# stm32.net
KiCad netlist of a schematic drawn in EasyEDA Pro
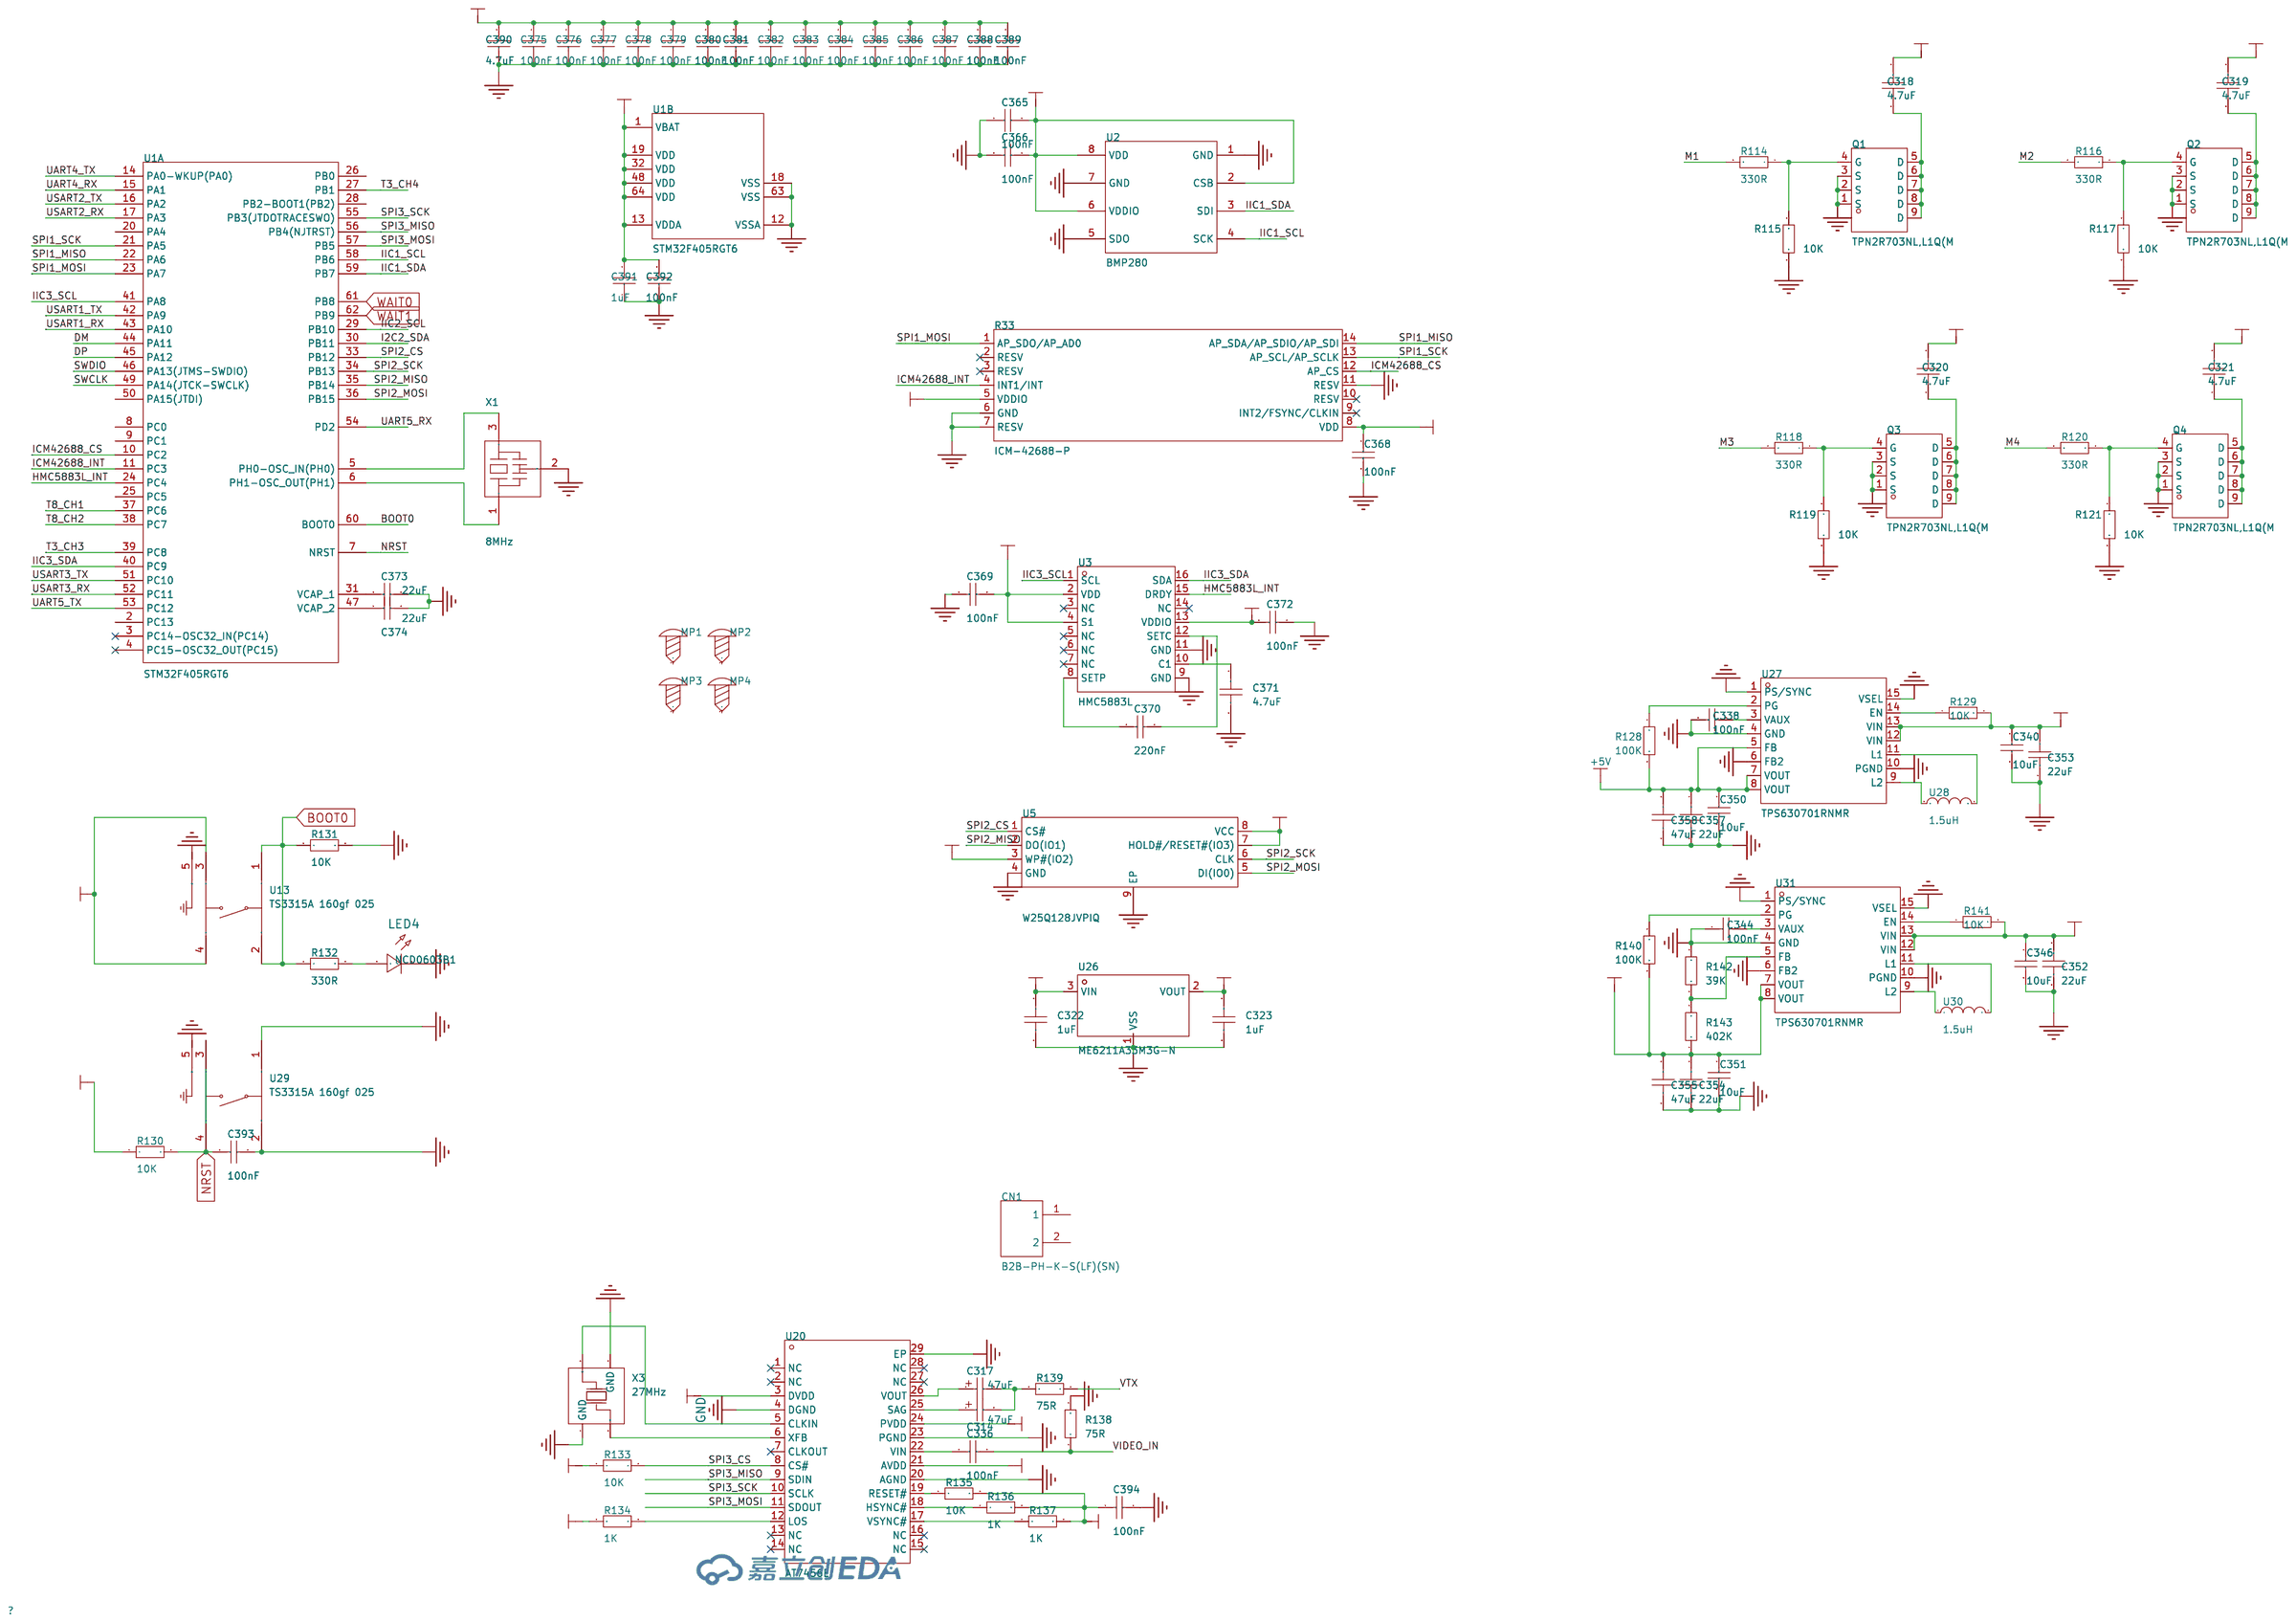
[diagram p0: P1]
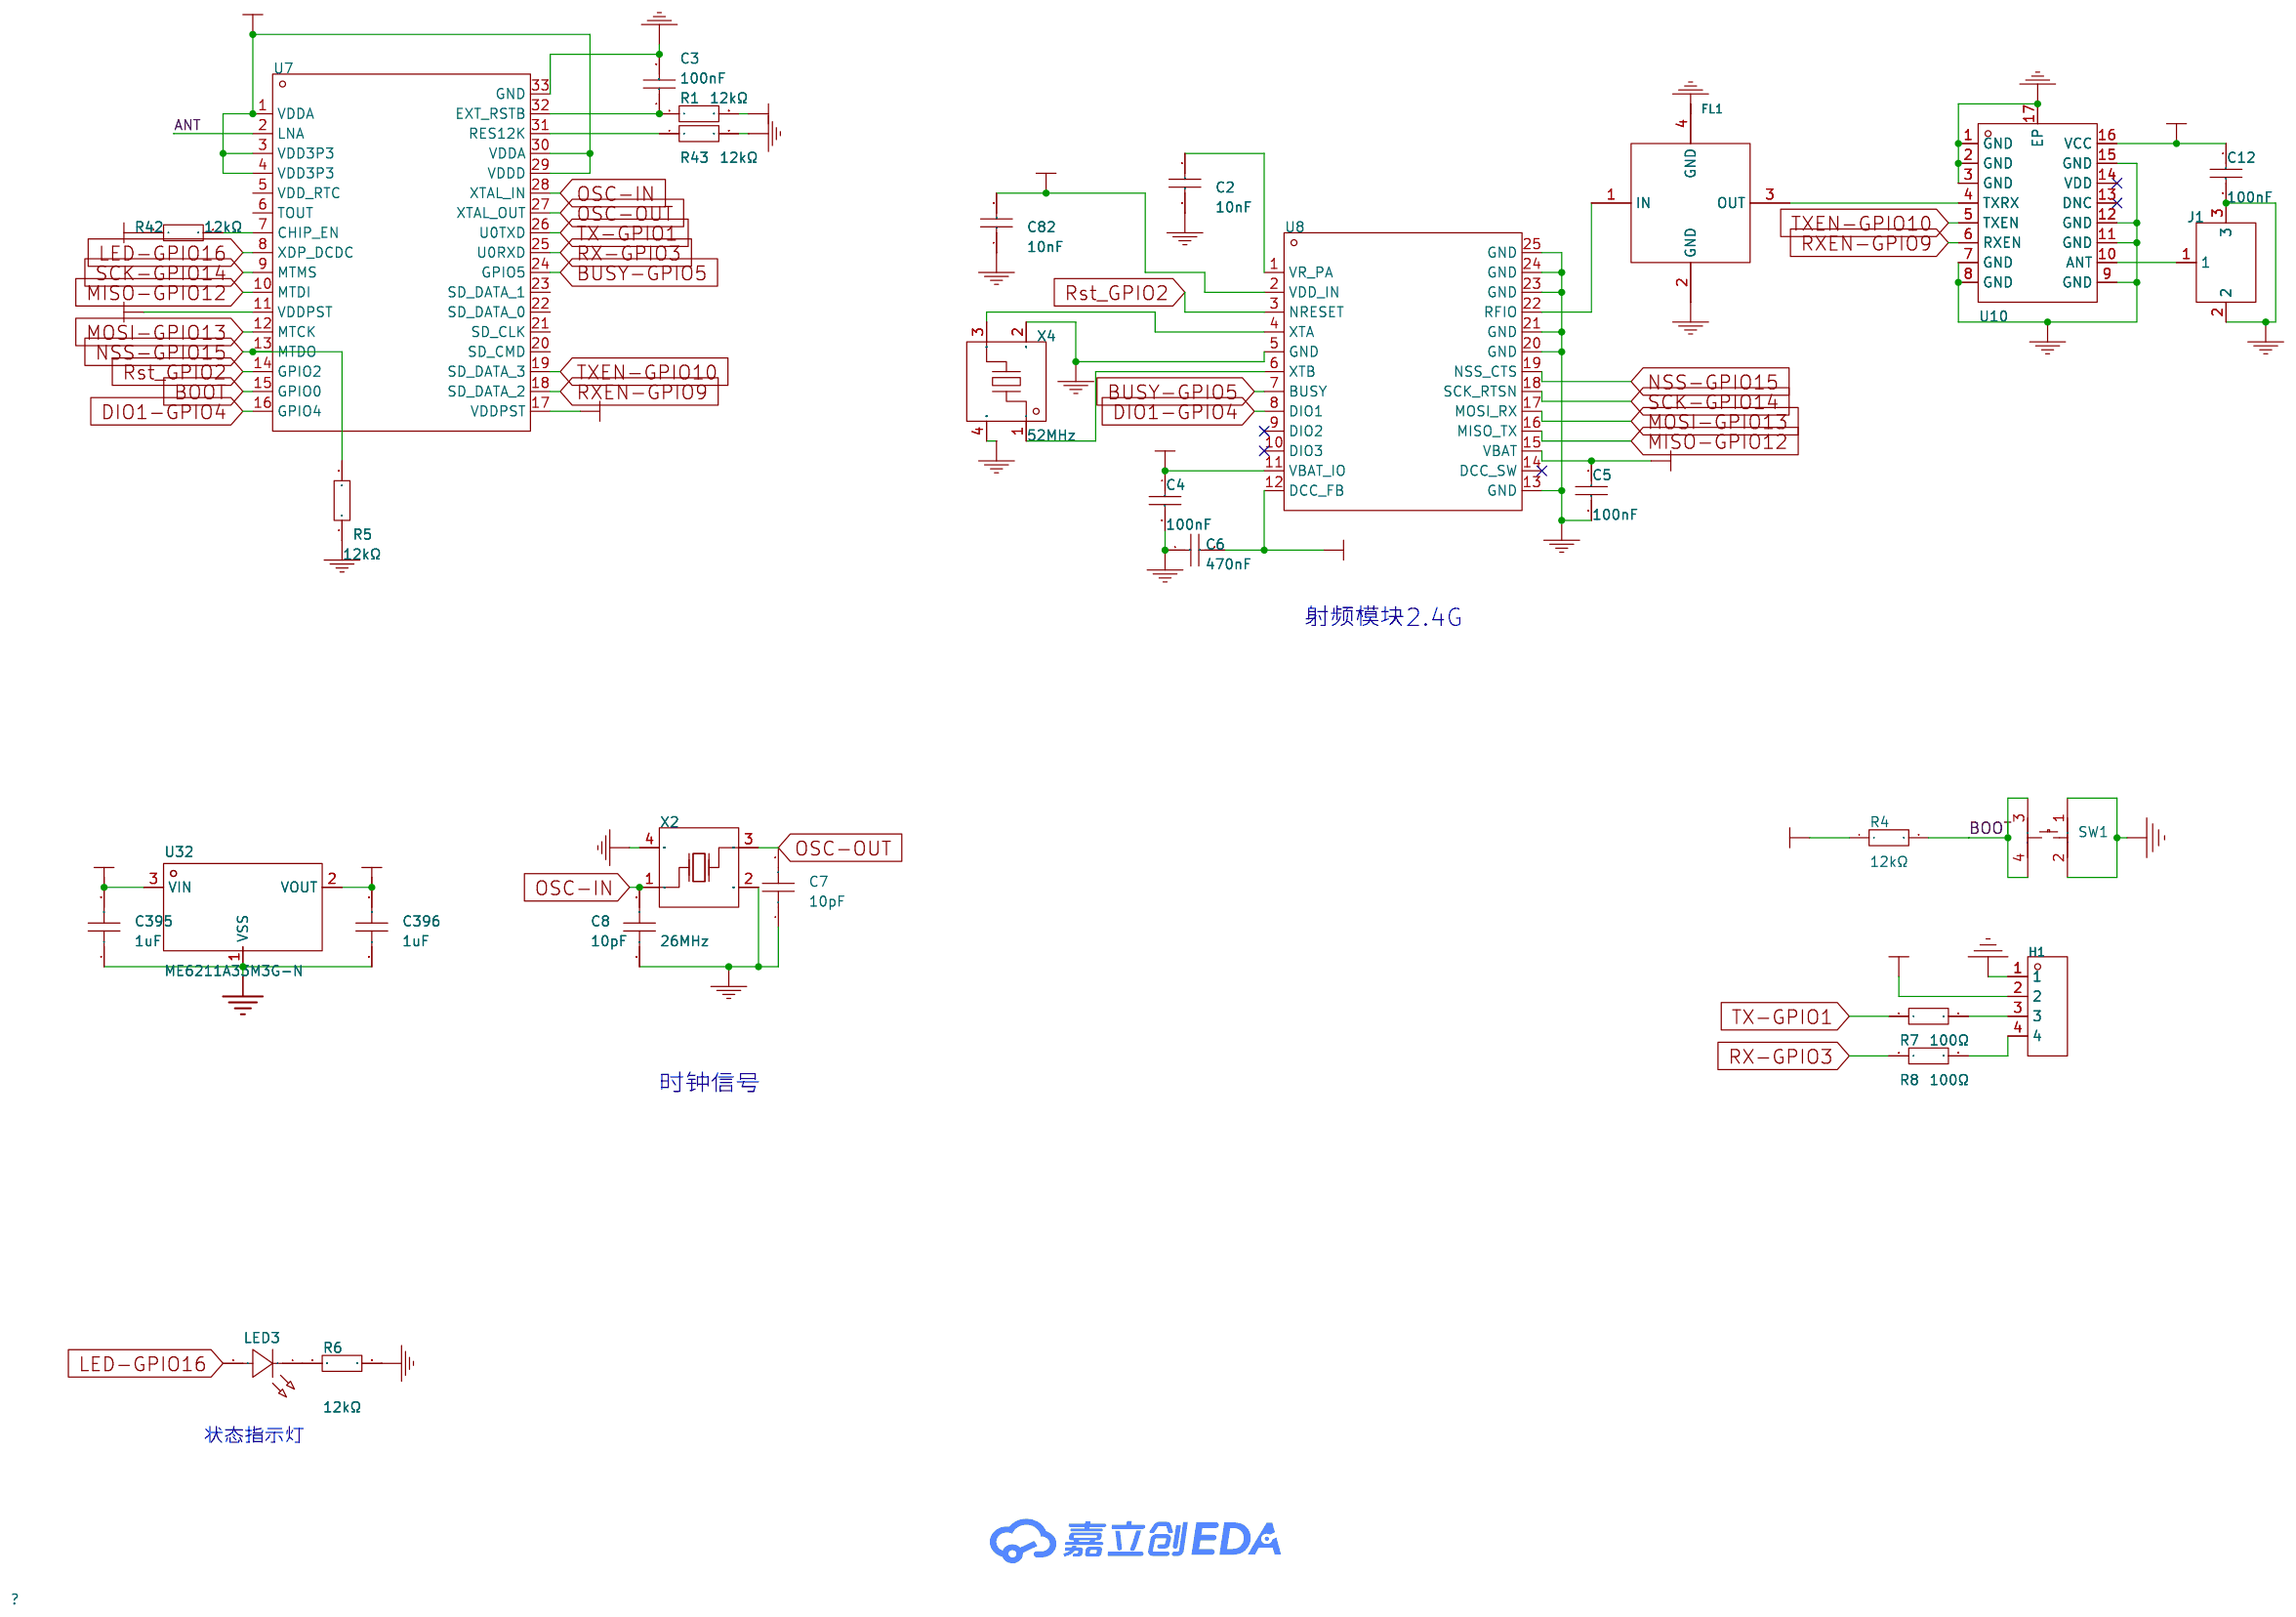
[diagram p1: P2]

(export (version "E")
  (design (tool "Eeschema 10.0.6"))
  (components
    (comp (ref "C314")
      (value "47uF")
      (footprint "easyedapro:CAP-SMD_L3.2-W1.6-RD")
      (description "容值:47uF;精度:±10%;额定电压:6.3V;等效串联电阻:2.5Ω@100kHz;")
      (fields (field (name "Manufacturer Part") "TC212A476K006Y") (field (name "Manufacturer") "Sunlord(顺络)"))
      (libsource (lib "easyedapro") (part "TC212A476K006Y"))
    )
    (comp (ref "C317")
      (value "47uF")
      (footprint "easyedapro:CAP-SMD_L3.2-W1.6-RD")
      (description "容值:47uF;精度:±10%;额定电压:6.3V;等效串联电阻:2.5Ω@100kHz;")
      (fields (field (name "Manufacturer Part") "TC212A476K006Y") (field (name "Manufacturer") "Sunlord(顺络)"))
      (libsource (lib "easyedapro") (part "TC212A476K006Y"))
    )
    (comp (ref "C318")
      (value "4.7uF")
      (footprint "easyedapro:C0805")
      (libsource (lib "easyedapro") (part "Capacitance"))
    )
    (comp (ref "C319")
      (value "4.7uF")
      (footprint "easyedapro:C0805")
      (libsource (lib "easyedapro") (part "Capacitance"))
    )
    (comp (ref "C320")
      (value "4.7uF")
      (footprint "easyedapro:C0805")
      (libsource (lib "easyedapro") (part "Capacitance"))
    )
    (comp (ref "C321")
      (value "4.7uF")
      (footprint "easyedapro:C0805")
      (libsource (lib "easyedapro") (part "Capacitance"))
    )
    (comp (ref "C322")
      (value "1uF")
      (footprint "easyedapro:C0402")
      (description "容值:10pF;精度:±5%;额定电压:50V;材质(温度系数):C0G;")
      (fields
        (field (name "Manufacturer Part") "CL05C100JB5NNNC")
        (field (name "Manufacturer") "SAMSUNG(三星)")
      )
      (libsource (lib "easyedapro") (part "CL05C100JB5NNNC"))
    )
    (comp (ref "C323")
      (value "1uF")
      (footprint "easyedapro:C0402")
      (description "容值:10pF;精度:±5%;额定电压:50V;材质(温度系数):C0G;")
      (fields
        (field (name "Manufacturer Part") "CL05C100JB5NNNC")
        (field (name "Manufacturer") "SAMSUNG(三星)")
      )
      (libsource (lib "easyedapro") (part "CL05C100JB5NNNC"))
    )
    (comp (ref "C336")
      (value "100nF")
      (footprint "easyedapro:C0402")
      (description "容值:100nF;精度:±10%;额定电压:16V;材质(温度系数):X7R;")
      (fields
        (field (name "Manufacturer Part") "CL05B104KO5NNNC")
        (field (name "Manufacturer") "SAMSUNG(三星)")
      )
      (libsource (lib "easyedapro") (part "CL05B104KO5NNNC"))
    )
    (comp (ref "C338")
      (value "100nF")
      (footprint "easyedapro:C0402")
      (description "容值:100nF;精度:±10%;额定电压:16V;材质(温度系数):X7R;")
      (fields
        (field (name "Manufacturer Part") "CL05B104KO5NNNC")
        (field (name "Manufacturer") "SAMSUNG(三星)")
      )
      (libsource (lib "easyedapro") (part "CL05B104KO5NNNC"))
    )
    (comp (ref "C340")
      (value "10uF")
      (footprint "easyedapro:C0402")
      (description "容值:100nF;精度:±10%;额定电压:16V;材质(温度系数):X7R;")
      (fields
        (field (name "Manufacturer Part") "CL05B104KO5NNNC")
        (field (name "Manufacturer") "SAMSUNG(三星)")
      )
      (libsource (lib "easyedapro") (part "CL05B104KO5NNNC"))
    )
    (comp (ref "C344")
      (value "100nF")
      (footprint "easyedapro:C0402")
      (description "容值:100nF;精度:±10%;额定电压:16V;材质(温度系数):X7R;")
      (fields
        (field (name "Manufacturer Part") "CL05B104KO5NNNC")
        (field (name "Manufacturer") "SAMSUNG(三星)")
      )
      (libsource (lib "easyedapro") (part "CL05B104KO5NNNC"))
    )
    (comp (ref "C346")
      (value "10uF")
      (footprint "easyedapro:C0402")
      (description "容值:100nF;精度:±10%;额定电压:16V;材质(温度系数):X7R;")
      (fields
        (field (name "Manufacturer Part") "CL05B104KO5NNNC")
        (field (name "Manufacturer") "SAMSUNG(三星)")
      )
      (libsource (lib "easyedapro") (part "CL05B104KO5NNNC"))
    )
    (comp (ref "C350")
      (value "10uF")
      (footprint "easyedapro:C0402")
      (description "容值:100nF;精度:±10%;额定电压:16V;材质(温度系数):X7R;")
      (fields
        (field (name "Manufacturer Part") "CL05B104KO5NNNC")
        (field (name "Manufacturer") "SAMSUNG(三星)")
      )
      (libsource (lib "easyedapro") (part "CL05B104KO5NNNC"))
    )
    (comp (ref "C351")
      (value "10uF")
      (footprint "easyedapro:C0402")
      (description "容值:100nF;精度:±10%;额定电压:16V;材质(温度系数):X7R;")
      (fields
        (field (name "Manufacturer Part") "CL05B104KO5NNNC")
        (field (name "Manufacturer") "SAMSUNG(三星)")
      )
      (libsource (lib "easyedapro") (part "CL05B104KO5NNNC"))
    )
    (comp (ref "C352")
      (value "22uF")
      (footprint "easyedapro:C0805")
      (libsource (lib "easyedapro") (part "Capacitance"))
    )
    (comp (ref "C353")
      (value "22uF")
      (footprint "easyedapro:C0805")
      (libsource (lib "easyedapro") (part "Capacitance"))
    )
    (comp (ref "C354")
      (value "22uF")
      (footprint "easyedapro:C0805")
      (libsource (lib "easyedapro") (part "Capacitance"))
    )
    (comp (ref "C355")
      (value "47uF")
      (footprint "easyedapro:C0805")
      (libsource (lib "easyedapro") (part "Capacitance"))
    )
    (comp (ref "C357")
      (value "22uF")
      (footprint "easyedapro:C0805")
      (libsource (lib "easyedapro") (part "Capacitance"))
    )
    (comp (ref "C358")
      (value "47uF")
      (footprint "easyedapro:C0805")
      (libsource (lib "easyedapro") (part "Capacitance"))
    )
    (comp (ref "C365")
      (value "100nF")
      (footprint "easyedapro:C0402")
      (description "容值:100nF;精度:±10%;额定电压:16V;材质(温度系数):X7R;")
      (fields
        (field (name "Manufacturer Part") "CL05B104KO5NNNC")
        (field (name "Manufacturer") "SAMSUNG(三星)")
      )
      (libsource (lib "easyedapro") (part "CL05B104KO5NNNC"))
    )
    (comp (ref "C366")
      (value "100nF")
      (footprint "easyedapro:C0402")
      (description "容值:100nF;精度:±10%;额定电压:16V;材质(温度系数):X7R;")
      (fields
        (field (name "Manufacturer Part") "CL05B104KO5NNNC")
        (field (name "Manufacturer") "SAMSUNG(三星)")
      )
      (libsource (lib "easyedapro") (part "CL05B104KO5NNNC"))
    )
    (comp (ref "C368")
      (value "100nF")
      (footprint "easyedapro:C0402")
      (description "容值:100nF;精度:±10%;额定电压:16V;材质(温度系数):X7R;")
      (fields
        (field (name "Manufacturer Part") "CL05B104KO5NNNC")
        (field (name "Manufacturer") "SAMSUNG(三星)")
      )
      (libsource (lib "easyedapro") (part "CL05B104KO5NNNC"))
    )
    (comp (ref "C369")
      (value "100nF")
      (footprint "easyedapro:C0402")
      (description "容值:100nF;精度:±10%;额定电压:16V;材质(温度系数):X7R;")
      (fields
        (field (name "Manufacturer Part") "CL05B104KO5NNNC")
        (field (name "Manufacturer") "SAMSUNG(三星)")
      )
      (libsource (lib "easyedapro") (part "CL05B104KO5NNNC"))
    )
    (comp (ref "C370")
      (value "220nF")
      (footprint "easyedapro:C0402")
      (description "容值:100nF;精度:±10%;额定电压:16V;材质(温度系数):X7R;")
      (fields
        (field (name "Manufacturer Part") "CL05B104KO5NNNC")
        (field (name "Manufacturer") "SAMSUNG(三星)")
      )
      (libsource (lib "easyedapro") (part "CL05B104KO5NNNC"))
    )
    (comp (ref "C371")
      (value "4.7uF")
      (footprint "easyedapro:C0805")
      (libsource (lib "easyedapro") (part "Capacitance"))
    )
    (comp (ref "C372")
      (value "100nF")
      (footprint "easyedapro:C0402")
      (description "容值:100nF;精度:±10%;额定电压:16V;材质(温度系数):X7R;")
      (fields
        (field (name "Manufacturer Part") "CL05B104KO5NNNC")
        (field (name "Manufacturer") "SAMSUNG(三星)")
      )
      (libsource (lib "easyedapro") (part "CL05B104KO5NNNC"))
    )
    (comp (ref "C373")
      (value "22uF")
      (footprint "easyedapro:C0402")
      (description "容值:100nF;精度:±10%;额定电压:16V;材质(温度系数):X7R;")
      (fields
        (field (name "Manufacturer Part") "CL05B104KO5NNNC")
        (field (name "Manufacturer") "SAMSUNG(三星)")
      )
      (libsource (lib "easyedapro") (part "CL05B104KO5NNNC"))
    )
    (comp (ref "C374")
      (value "22uF")
      (footprint "easyedapro:C0402")
      (description "容值:100nF;精度:±10%;额定电压:16V;材质(温度系数):X7R;")
      (fields
        (field (name "Manufacturer Part") "CL05B104KO5NNNC")
        (field (name "Manufacturer") "SAMSUNG(三星)")
      )
      (libsource (lib "easyedapro") (part "CL05B104KO5NNNC"))
    )
    (comp (ref "C375")
      (value "100nF")
      (footprint "easyedapro:C0402")
      (description "容值:100nF;精度:±10%;额定电压:16V;材质(温度系数):X7R;")
      (fields
        (field (name "Manufacturer Part") "CL05B104KO5NNNC")
        (field (name "Manufacturer") "SAMSUNG(三星)")
      )
      (libsource (lib "easyedapro") (part "CL05B104KO5NNNC"))
    )
    (comp (ref "C376")
      (value "100nF")
      (footprint "easyedapro:C0402")
      (description "容值:100nF;精度:±10%;额定电压:16V;材质(温度系数):X7R;")
      (fields
        (field (name "Manufacturer Part") "CL05B104KO5NNNC")
        (field (name "Manufacturer") "SAMSUNG(三星)")
      )
      (libsource (lib "easyedapro") (part "CL05B104KO5NNNC"))
    )
    (comp (ref "C377")
      (value "100nF")
      (footprint "easyedapro:C0402")
      (description "容值:100nF;精度:±10%;额定电压:16V;材质(温度系数):X7R;")
      (fields
        (field (name "Manufacturer Part") "CL05B104KO5NNNC")
        (field (name "Manufacturer") "SAMSUNG(三星)")
      )
      (libsource (lib "easyedapro") (part "CL05B104KO5NNNC"))
    )
    (comp (ref "C378")
      (value "100nF")
      (footprint "easyedapro:C0402")
      (description "容值:100nF;精度:±10%;额定电压:16V;材质(温度系数):X7R;")
      (fields
        (field (name "Manufacturer Part") "CL05B104KO5NNNC")
        (field (name "Manufacturer") "SAMSUNG(三星)")
      )
      (libsource (lib "easyedapro") (part "CL05B104KO5NNNC"))
    )
    (comp (ref "C379")
      (value "100nF")
      (footprint "easyedapro:C0402")
      (description "容值:100nF;精度:±10%;额定电压:16V;材质(温度系数):X7R;")
      (fields
        (field (name "Manufacturer Part") "CL05B104KO5NNNC")
        (field (name "Manufacturer") "SAMSUNG(三星)")
      )
      (libsource (lib "easyedapro") (part "CL05B104KO5NNNC"))
    )
    (comp (ref "C380")
      (value "100nF")
      (footprint "easyedapro:C0402")
      (description "容值:100nF;精度:±10%;额定电压:16V;材质(温度系数):X7R;")
      (fields
        (field (name "Manufacturer Part") "CL05B104KO5NNNC")
        (field (name "Manufacturer") "SAMSUNG(三星)")
      )
      (libsource (lib "easyedapro") (part "CL05B104KO5NNNC"))
    )
    (comp (ref "C381")
      (value "100nF")
      (footprint "easyedapro:C0402")
      (description "容值:100nF;精度:±10%;额定电压:16V;材质(温度系数):X7R;")
      (fields
        (field (name "Manufacturer Part") "CL05B104KO5NNNC")
        (field (name "Manufacturer") "SAMSUNG(三星)")
      )
      (libsource (lib "easyedapro") (part "CL05B104KO5NNNC"))
    )
    (comp (ref "C382")
      (value "100nF")
      (footprint "easyedapro:C0402")
      (description "容值:100nF;精度:±10%;额定电压:16V;材质(温度系数):X7R;")
      (fields
        (field (name "Manufacturer Part") "CL05B104KO5NNNC")
        (field (name "Manufacturer") "SAMSUNG(三星)")
      )
      (libsource (lib "easyedapro") (part "CL05B104KO5NNNC"))
    )
    (comp (ref "C383")
      (value "100nF")
      (footprint "easyedapro:C0402")
      (description "容值:100nF;精度:±10%;额定电压:16V;材质(温度系数):X7R;")
      (fields
        (field (name "Manufacturer Part") "CL05B104KO5NNNC")
        (field (name "Manufacturer") "SAMSUNG(三星)")
      )
      (libsource (lib "easyedapro") (part "CL05B104KO5NNNC"))
    )
    (comp (ref "C384")
      (value "100nF")
      (footprint "easyedapro:C0402")
      (description "容值:100nF;精度:±10%;额定电压:16V;材质(温度系数):X7R;")
      (fields
        (field (name "Manufacturer Part") "CL05B104KO5NNNC")
        (field (name "Manufacturer") "SAMSUNG(三星)")
      )
      (libsource (lib "easyedapro") (part "CL05B104KO5NNNC"))
    )
    (comp (ref "C385")
      (value "100nF")
      (footprint "easyedapro:C0402")
      (description "容值:100nF;精度:±10%;额定电压:16V;材质(温度系数):X7R;")
      (fields
        (field (name "Manufacturer Part") "CL05B104KO5NNNC")
        (field (name "Manufacturer") "SAMSUNG(三星)")
      )
      (libsource (lib "easyedapro") (part "CL05B104KO5NNNC"))
    )
    (comp (ref "C386")
      (value "100nF")
      (footprint "easyedapro:C0402")
      (description "容值:100nF;精度:±10%;额定电压:16V;材质(温度系数):X7R;")
      (fields
        (field (name "Manufacturer Part") "CL05B104KO5NNNC")
        (field (name "Manufacturer") "SAMSUNG(三星)")
      )
      (libsource (lib "easyedapro") (part "CL05B104KO5NNNC"))
    )
    (comp (ref "C387")
      (value "100nF")
      (footprint "easyedapro:C0402")
      (description "容值:100nF;精度:±10%;额定电压:16V;材质(温度系数):X7R;")
      (fields
        (field (name "Manufacturer Part") "CL05B104KO5NNNC")
        (field (name "Manufacturer") "SAMSUNG(三星)")
      )
      (libsource (lib "easyedapro") (part "CL05B104KO5NNNC"))
    )
    (comp (ref "C388")
      (value "100nF")
      (footprint "easyedapro:C0402")
      (description "容值:100nF;精度:±10%;额定电压:16V;材质(温度系数):X7R;")
      (fields
        (field (name "Manufacturer Part") "CL05B104KO5NNNC")
        (field (name "Manufacturer") "SAMSUNG(三星)")
      )
      (libsource (lib "easyedapro") (part "CL05B104KO5NNNC"))
    )
    (comp (ref "C389")
      (value "100nF")
      (footprint "easyedapro:C0402")
      (description "容值:100nF;精度:±10%;额定电压:16V;材质(温度系数):X7R;")
      (fields
        (field (name "Manufacturer Part") "CL05B104KO5NNNC")
        (field (name "Manufacturer") "SAMSUNG(三星)")
      )
      (libsource (lib "easyedapro") (part "CL05B104KO5NNNC"))
    )
    (comp (ref "C390")
      (value "4.7uF")
      (footprint "easyedapro:C0402")
      (description "容值:100nF;精度:±10%;额定电压:16V;材质(温度系数):X7R;")
      (fields
        (field (name "Manufacturer Part") "CL05B104KO5NNNC")
        (field (name "Manufacturer") "SAMSUNG(三星)")
      )
      (libsource (lib "easyedapro") (part "CL05B104KO5NNNC"))
    )
    (comp (ref "C391")
      (value "1uF")
      (footprint "easyedapro:C0402")
      (description "容值:100nF;精度:±10%;额定电压:16V;材质(温度系数):X7R;")
      (fields
        (field (name "Manufacturer Part") "CL05B104KO5NNNC")
        (field (name "Manufacturer") "SAMSUNG(三星)")
      )
      (libsource (lib "easyedapro") (part "CL05B104KO5NNNC"))
    )
    (comp (ref "C392")
      (value "100nF")
      (footprint "easyedapro:C0402")
      (description "容值:100nF;精度:±10%;额定电压:16V;材质(温度系数):X7R;")
      (fields
        (field (name "Manufacturer Part") "CL05B104KO5NNNC")
        (field (name "Manufacturer") "SAMSUNG(三星)")
      )
      (libsource (lib "easyedapro") (part "CL05B104KO5NNNC"))
    )
    (comp (ref "C393")
      (value "100nF")
      (footprint "easyedapro:C0402")
      (description "容值:100nF;精度:±10%;额定电压:16V;材质(温度系数):X7R;")
      (fields
        (field (name "Manufacturer Part") "CL05B104KO5NNNC")
        (field (name "Manufacturer") "SAMSUNG(三星)")
      )
      (libsource (lib "easyedapro") (part "CL05B104KO5NNNC"))
    )
    (comp (ref "C394")
      (value "100nF")
      (footprint "easyedapro:C0402")
      (description "容值:100nF;精度:±10%;额定电压:16V;材质(温度系数):X7R;")
      (fields
        (field (name "Manufacturer Part") "CL05B104KO5NNNC")
        (field (name "Manufacturer") "SAMSUNG(三星)")
      )
      (libsource (lib "easyedapro") (part "CL05B104KO5NNNC"))
    )
    (comp (ref "CN1")
      (value "B2B-PH-K-S(LF)(SN)")
      (footprint "easyedapro:CONN-TH_B2B-PH-K-S")
      (fields (field (name "Manufacturer") "JST"))
      (libsource (lib "easyedapro") (part "B2B-PH-K-S(LF)(SN)"))
    )
    (comp (ref "LED4")
      (value "NCD0603B1")
      (fields (field (name "Manufacturer") "国星光电"))
      (libsource (lib "easyedapro") (part "LED_R"))
    )
    (comp (ref "MP1")
      (value "M2螺丝")
      (footprint "easyedapro:M2螺丝")
      (libsource (lib "easyedapro") (part "螺丝孔"))
    )
    (comp (ref "MP2")
      (value "M2螺丝")
      (footprint "easyedapro:M2螺丝")
      (libsource (lib "easyedapro") (part "螺丝孔"))
    )
    (comp (ref "MP3")
      (value "M2螺丝")
      (footprint "easyedapro:M2螺丝")
      (libsource (lib "easyedapro") (part "螺丝孔"))
    )
    (comp (ref "MP4")
      (value "M2螺丝")
      (footprint "easyedapro:M2螺丝")
      (libsource (lib "easyedapro") (part "螺丝孔"))
    )
    (comp (ref "Q1")
      (value "TPN2R703NL,L1Q(M")
      (footprint "easyedapro:TSON-8_L3.1-W3.1-P0.65-LS3.3-BL-EP")
      (fields (field (name "Manufacturer") "TOSHIBA(东芝)"))
      (libsource (lib "easyedapro") (part "TPN2R703NL,L1Q(M"))
    )
    (comp (ref "Q2")
      (value "TPN2R703NL,L1Q(M")
      (footprint "easyedapro:TSON-8_L3.1-W3.1-P0.65-LS3.3-BL-EP")
      (fields (field (name "Manufacturer") "TOSHIBA(东芝)"))
      (libsource (lib "easyedapro") (part "TPN2R703NL,L1Q(M"))
    )
    (comp (ref "Q3")
      (value "TPN2R703NL,L1Q(M")
      (footprint "easyedapro:TSON-8_L3.1-W3.1-P0.65-LS3.3-BL-EP")
      (fields (field (name "Manufacturer") "TOSHIBA(东芝)"))
      (libsource (lib "easyedapro") (part "TPN2R703NL,L1Q(M"))
    )
    (comp (ref "Q4")
      (value "TPN2R703NL,L1Q(M")
      (footprint "easyedapro:TSON-8_L3.1-W3.1-P0.65-LS3.3-BL-EP")
      (fields (field (name "Manufacturer") "TOSHIBA(东芝)"))
      (libsource (lib "easyedapro") (part "TPN2R703NL,L1Q(M"))
    )
    (comp (ref "R33")
      (value "ICM-42688-P")
      (fields (field (name "Manufacturer") "TDK InvenSense(应美盛)"))
      (libsource (lib "easyedapro") (part "ICM-42688-P"))
    )
    (comp (ref "R114")
      (value "330R")
      (footprint "easyedapro:R0402")
      (libsource (lib "easyedapro") (part "电阻"))
    )
    (comp (ref "R115")
      (value "10K")
      (footprint "easyedapro:R0402")
      (libsource (lib "easyedapro") (part "电阻"))
    )
    (comp (ref "R116")
      (value "330R")
      (footprint "easyedapro:R0402")
      (libsource (lib "easyedapro") (part "电阻"))
    )
    (comp (ref "R117")
      (value "10K")
      (footprint "easyedapro:R0402")
      (libsource (lib "easyedapro") (part "电阻"))
    )
    (comp (ref "R118")
      (value "330R")
      (footprint "easyedapro:R0402")
      (libsource (lib "easyedapro") (part "电阻"))
    )
    (comp (ref "R119")
      (value "10K")
      (footprint "easyedapro:R0402")
      (libsource (lib "easyedapro") (part "电阻"))
    )
    (comp (ref "R120")
      (value "330R")
      (footprint "easyedapro:R0402")
      (libsource (lib "easyedapro") (part "电阻"))
    )
    (comp (ref "R121")
      (value "10K")
      (footprint "easyedapro:R0402")
      (libsource (lib "easyedapro") (part "电阻"))
    )
    (comp (ref "R128")
      (value "100K")
      (footprint "easyedapro:R0402")
      (libsource (lib "easyedapro") (part "电阻"))
    )
    (comp (ref "R129")
      (value "10K")
      (footprint "easyedapro:R0402")
      (libsource (lib "easyedapro") (part "电阻"))
    )
    (comp (ref "R130")
      (value "10K")
      (footprint "easyedapro:R0402")
      (libsource (lib "easyedapro") (part "电阻"))
    )
    (comp (ref "R131")
      (value "10K")
      (footprint "easyedapro:R0402")
      (libsource (lib "easyedapro") (part "电阻"))
    )
    (comp (ref "R132")
      (value "330R")
      (footprint "easyedapro:R0402")
      (libsource (lib "easyedapro") (part "电阻"))
    )
    (comp (ref "R133")
      (value "10K")
      (footprint "easyedapro:R0402")
      (libsource (lib "easyedapro") (part "电阻"))
    )
    (comp (ref "R134") (value "1K") (footprint "easyedapro:R0402") (libsource (lib "easyedapro") (part "电阻")))
    (comp (ref "R135")
      (value "10K")
      (footprint "easyedapro:R0402")
      (libsource (lib "easyedapro") (part "电阻"))
    )
    (comp (ref "R136") (value "1K") (footprint "easyedapro:R0402") (libsource (lib "easyedapro") (part "电阻")))
    (comp (ref "R137") (value "1K") (footprint "easyedapro:R0402") (libsource (lib "easyedapro") (part "电阻")))
    (comp (ref "R138")
      (value "75R")
      (footprint "easyedapro:R0402")
      (libsource (lib "easyedapro") (part "电阻"))
    )
    (comp (ref "R139")
      (value "75R")
      (footprint "easyedapro:R0402")
      (libsource (lib "easyedapro") (part "电阻"))
    )
    (comp (ref "R140")
      (value "100K")
      (footprint "easyedapro:R0402")
      (libsource (lib "easyedapro") (part "电阻"))
    )
    (comp (ref "R141")
      (value "10K")
      (footprint "easyedapro:R0402")
      (libsource (lib "easyedapro") (part "电阻"))
    )
    (comp (ref "R142")
      (value "39K")
      (footprint "easyedapro:R0402")
      (libsource (lib "easyedapro") (part "电阻"))
    )
    (comp (ref "R143")
      (value "402K")
      (footprint "easyedapro:R0402")
      (libsource (lib "easyedapro") (part "电阻"))
    )
    (comp (ref "U1")
      (value "STM32F405RGT6")
      (footprint "easyedapro:LQFP-64_L10.0-W10.0-P0.50-LS12.0-BL")
      (description "CPU内核:ARM-M4;CPU最大主频:168MHz;应用领域:-;")
      (fields (field (name "Manufacturer") "ST(意法半导体)"))
      (libsource (lib "easyedapro") (part "STM32F405RGT6"))
    )
    (comp (ref "U2")
      (value "BMP280")
      (footprint "easyedapro:LGA-8_L2.5-W2.0-P0.65_AMP6127")
      (description "Bosch气压传感器新品，可测量大气压力，带高精度温度测量，可校准精确计算海拔高度。I2C或SPI接口，宽量程（300-1100hpa），精度高")
      (fields (field (name "Manufacturer") "Bosch(博世)"))
      (libsource (lib "easyedapro") (part "BMP280"))
    )
    (comp (ref "U3")
      (value "HMC5883L")
      (footprint "easyedapro:LPCC-16_L3.0-W3.0-P0.50-BL")
      (libsource (lib "easyedapro") (part "HMC5883L"))
    )
    (comp (ref "U5")
      (value "W25Q128JVPIQ")
      (footprint "easyedapro:WSON-8_L5.0-W6.0-P1.27-BL-EP")
      (description "接口类型:SPI;存储容量:128Mbit;时钟频率(fc):133MHz;")
      (fields (field (name "Manufacturer") "Winbond(华邦)"))
      (libsource (lib "easyedapro") (part "W25Q128JVPIQ"))
    )
    (comp (ref "U13")
      (value "TS3315A 160gf 025")
      (footprint "easyedapro:SW-SMD_4P-L3.4-W3.4-P2.00-LS4.0_TS3315A160GF")
      (fields (field (name "Manufacturer") "SHOU HAN(首韩)"))
      (libsource (lib "easyedapro") (part "TS3315A 160GF 025"))
    )
    (comp (ref "U20")
      (value "AT7456E")
      (fields (field (name "Manufacturer") "杭州中科微"))
      (libsource (lib "easyedapro") (part "at7456"))
    )
    (comp (ref "U26")
      (value "ME6211A33M3G-N")
      (footprint "easyedapro:SOT-23-3_L2.9-W1.6-P1.90-LS2.8-BR")
      (description "输出类型:固定;工作电压:6V;输出电压:3.3V;输出电流:500mA;电源纹波抑制比(PSRR):70dB@(1kHz);输出极性:正极;")
      (fields (field (name "Manufacturer") "MICRONE(南京微盟)"))
      (libsource (lib "easyedapro") (part "ME6211A33M3G-N"))
    )
    (comp (ref "U27")
      (value "TPS630701RNMR")
      (footprint "easyedapro:VQFN-HR-15_L3.0-W2.5-P0.50-BL_TPS63070RNMR")
      (description "功能类型:升降压型;工作电压:2V~16V;输出电压:5V;输出电流:2A;输出类型:固定;")
      (fields (field (name "Manufacturer") "TI(德州仪器)"))
      (libsource (lib "easyedapro") (part "TPS630701RNMR"))
    )
    (comp (ref "U28")
      (value "1.5uH")
      (footprint "easyedapro:IND-SMD_L2.5-W2.0_MEKK2520TR47M")
      (description "电感值:1.5uH;精度:±20%;额定电流:3.7A;饱和电流(Isat):4.5A;类型:-;")
      (fields
        (field (name "Manufacturer Part") "FTC252012S1R5MBCA")
        (field (name "Manufacturer") "cjiang(长江微电)")
      )
      (libsource (lib "easyedapro") (part "FTC252012S1R5MBCA"))
    )
    (comp (ref "U29")
      (value "TS3315A 160gf 025")
      (footprint "easyedapro:SW-SMD_4P-L3.4-W3.4-P2.00-LS4.0_TS3315A160GF")
      (fields (field (name "Manufacturer") "SHOU HAN(首韩)"))
      (libsource (lib "easyedapro") (part "TS3315A 160GF 025"))
    )
    (comp (ref "U30")
      (value "1.5uH")
      (footprint "easyedapro:IND-SMD_L2.5-W2.0_MEKK2520TR47M")
      (description "电感值:1.5uH;精度:±20%;额定电流:3.7A;饱和电流(Isat):4.5A;类型:-;")
      (fields
        (field (name "Manufacturer Part") "FTC252012S1R5MBCA")
        (field (name "Manufacturer") "cjiang(长江微电)")
      )
      (libsource (lib "easyedapro") (part "FTC252012S1R5MBCA"))
    )
    (comp (ref "U31")
      (value "TPS630701RNMR")
      (footprint "easyedapro:VQFN-HR-15_L3.0-W2.5-P0.50-BL_TPS63070RNMR")
      (description "功能类型:升降压型;工作电压:2V~16V;输出电压:5V;输出电流:2A;输出类型:固定;")
      (fields (field (name "Manufacturer") "TI(德州仪器)"))
      (libsource (lib "easyedapro") (part "TPS630701RNMR"))
    )
    (comp (ref "X1")
      (value "8MHz")
      (footprint "easyedapro:OSC-SMD_3P-L3.2-W1.3-P1.2-L")
      (description "频率:8MHz;频率容差:±0.5%;内置负载电容:33pF;谐振阻抗:-;")
      (fields (field (name "Manufacturer Part") "CSTCE8M00G55-R0") (field (name "Manufacturer") "muRata(村田)"))
      (libsource (lib "easyedapro") (part "CSTCE8M00G55-R0"))
    )
    (comp (ref "X3")
      (value "27MHz")
      (footprint "easyedapro:OSC-SMD_4P-L3.2-W2.5-BL")
      (description "频率:27MHz;晶振类型:贴片无源晶振;负载电容:10pF;等效串联电阻(ESR):40Ω;频率公差:±10ppm;频率稳定度:-;工作温度:-40°C~+85°C;")
      (fields (field (name "Manufacturer Part") "X1E000021015800") (field (name "Manufacturer") "EPSON(爱普生)"))
      (libsource (lib "easyedapro") (part "X1E000021015812"))
    )
    (comp (ref "C2")
      (value "10nF")
      (footprint "easyedapro:C0402")
      (description "容值:10nF;精度:±10%;额定电压:50V;材质(温度系数):X7R;")
      (fields
        (field (name "Manufacturer Part") "CL05B103KB5NNNC")
        (field (name "Manufacturer") "SAMSUNG(三星)")
      )
      (libsource (lib "easyedapro") (part "CL05B103KB5NNNC"))
    )
    (comp (ref "C3")
      (value "100nF")
      (footprint "easyedapro:C0402")
      (description "容值:100nF;精度:±10%;额定电压:16V;材质(温度系数):X7R;")
      (fields
        (field (name "Manufacturer Part") "CL05B104KO5NNNC")
        (field (name "Manufacturer") "SAMSUNG(三星)")
      )
      (libsource (lib "easyedapro") (part "CL05B104KO5NNNC"))
    )
    (comp (ref "C4")
      (value "100nF")
      (footprint "easyedapro:C0402")
      (description "容值:100nF;精度:±10%;额定电压:16V;材质(温度系数):X7R;")
      (fields
        (field (name "Manufacturer Part") "CL05B104KO5NNNC")
        (field (name "Manufacturer") "SAMSUNG(三星)")
      )
      (libsource (lib "easyedapro") (part "CL05B104KO5NNNC"))
    )
    (comp (ref "C5")
      (value "100nF")
      (footprint "easyedapro:C0402")
      (description "容值:100nF;精度:±10%;额定电压:16V;材质(温度系数):X7R;")
      (fields
        (field (name "Manufacturer Part") "CL05B104KO5NNNC")
        (field (name "Manufacturer") "SAMSUNG(三星)")
      )
      (libsource (lib "easyedapro") (part "CL05B104KO5NNNC"))
    )
    (comp (ref "C6")
      (value "470nF")
      (footprint "easyedapro:C0402")
      (description "容值:470nF;精度:±10%;额定电压:10V;材质(温度系数):X5R;")
      (fields
        (field (name "Manufacturer Part") "CL05A474KP5NNNC")
        (field (name "Manufacturer") "SAMSUNG(三星)")
      )
      (libsource (lib "easyedapro") (part "CL05A474KP5NNNC"))
    )
    (comp (ref "C7")
      (value "10pF")
      (footprint "easyedapro:C0402")
      (description "容值:10pF;精度:±5%;额定电压:50V;材质(温度系数):C0G;")
      (fields
        (field (name "Manufacturer Part") "CL05C100JB5NNNC")
        (field (name "Manufacturer") "SAMSUNG(三星)")
      )
      (libsource (lib "easyedapro") (part "CL05C100JB5NNNC"))
    )
    (comp (ref "C8")
      (value "10pF")
      (footprint "easyedapro:C0402")
      (description "容值:10pF;精度:±5%;额定电压:50V;材质(温度系数):C0G;")
      (fields
        (field (name "Manufacturer Part") "CL05C100JB5NNNC")
        (field (name "Manufacturer") "SAMSUNG(三星)")
      )
      (libsource (lib "easyedapro") (part "CL05C100JB5NNNC"))
    )
    (comp (ref "C12")
      (value "100nF")
      (footprint "easyedapro:C0402")
      (description "容值:100nF;精度:±10%;额定电压:16V;材质(温度系数):X7R;")
      (fields
        (field (name "Manufacturer Part") "CL05B104KO5NNNC")
        (field (name "Manufacturer") "SAMSUNG(三星)")
      )
      (libsource (lib "easyedapro") (part "CL05B104KO5NNNC"))
    )
    (comp (ref "C82")
      (value "10nF")
      (footprint "easyedapro:C0402")
      (description "容值:10nF;精度:±10%;额定电压:50V;材质(温度系数):X7R;")
      (fields
        (field (name "Manufacturer Part") "CL05B103KB5NNNC")
        (field (name "Manufacturer") "SAMSUNG(三星)")
      )
      (libsource (lib "easyedapro") (part "CL05B103KB5NNNC"))
    )
    (comp (ref "C395")
      (value "1uF")
      (footprint "easyedapro:C0402")
      (description "容值:10pF;精度:±5%;额定电压:50V;材质(温度系数):C0G;")
      (fields
        (field (name "Manufacturer Part") "CL05C100JB5NNNC")
        (field (name "Manufacturer") "SAMSUNG(三星)")
      )
      (libsource (lib "easyedapro") (part "CL05C100JB5NNNC"))
    )
    (comp (ref "C396")
      (value "1uF")
      (footprint "easyedapro:C0402")
      (description "容值:10pF;精度:±5%;额定电压:50V;材质(温度系数):C0G;")
      (fields
        (field (name "Manufacturer Part") "CL05C100JB5NNNC")
        (field (name "Manufacturer") "SAMSUNG(三星)")
      )
      (libsource (lib "easyedapro") (part "CL05C100JB5NNNC"))
    )
    (comp (ref "FL1")
      (value "2450FM07D0034T")
      (footprint "easyedapro:FILTER-SMD_4P-L1.0-W0.5-L")
      (description "带宽:100MHz;插入损耗:0.75dB;")
      (fields (field (name "Manufacturer") "JOHANSON(约翰逊)"))
      (libsource (lib "easyedapro") (part "2450FM07D0034T"))
    )
    (comp (ref "H1")
      (value "PZ254V-11-04P")
      (footprint "easyedapro:HDR-TH_4P-P2.54-V-M")
      (fields (field (name "Manufacturer") "XFCN(兴飞)"))
      (libsource (lib "easyedapro") (part "PZ254V-11-04P_C2691448"))
    )
    (comp (ref "J1")
      (value "BWU.FL-IPEX1")
      (footprint "easyedapro:IPEX-SMD_BWIPX-1-001E")
      (description "连接器类型:板端;接口类型:内针;频率-最大值:6GHz;接口直径:2mm;射频系列:IPEX;端口数量:1;阻抗:50Ω;接口长度/高度:1.25mm;工作温度范围:260°C;")
      (fields (field (name "Manufacturer") "BAT WIRELESS(蝙蝠无线)"))
      (libsource (lib "easyedapro") (part "BWU.FL-IPEX1"))
    )
    (comp (ref "LED3")
      (value "XL-1005UGC")
      (footprint "easyedapro:LED0402-RD_GREEN")
      (description "发光颜色:翠绿;主波长:516nm;色温:-;功率:80mW;安装方式:正贴;")
      (fields (field (name "Manufacturer") "XINGLIGHT(成兴光)"))
      (libsource (lib "easyedapro") (part "XL-1005UGC_C2856703"))
    )
    (comp (ref "R1")
      (value "12kΩ")
      (footprint "easyedapro:R0402")
      (description "电阻类型:厚膜电阻;阻值:12kΩ;精度:±1%;功率:62.5mW;")
      (fields
        (field (name "Manufacturer Part") "0402WGF1202TCE")
        (field (name "Manufacturer") "UNI-ROYAL(厚声)")
      )
      (libsource (lib "easyedapro") (part "0402WGF1202TCE"))
    )
    (comp (ref "R4")
      (value "12kΩ")
      (footprint "easyedapro:R0402")
      (description "电阻类型:厚膜电阻;阻值:12kΩ;精度:±1%;功率:62.5mW;")
      (fields
        (field (name "Manufacturer Part") "0402WGF1202TCE")
        (field (name "Manufacturer") "UNI-ROYAL(厚声)")
      )
      (libsource (lib "easyedapro") (part "0402WGF1202TCE"))
    )
    (comp (ref "R5")
      (value "12kΩ")
      (footprint "easyedapro:R0402")
      (description "电阻类型:厚膜电阻;阻值:12kΩ;精度:±1%;功率:62.5mW;")
      (fields
        (field (name "Manufacturer Part") "0402WGF1202TCE")
        (field (name "Manufacturer") "UNI-ROYAL(厚声)")
      )
      (libsource (lib "easyedapro") (part "0402WGF1202TCE"))
    )
    (comp (ref "R6")
      (value "12kΩ")
      (footprint "easyedapro:R0402")
      (description "电阻类型:厚膜电阻;阻值:12kΩ;精度:±1%;功率:62.5mW;")
      (fields
        (field (name "Manufacturer Part") "0402WGF1202TCE")
        (field (name "Manufacturer") "UNI-ROYAL(厚声)")
      )
      (libsource (lib "easyedapro") (part "0402WGF1202TCE"))
    )
    (comp (ref "R7")
      (value "100Ω")
      (footprint "easyedapro:R0402")
      (description "阻值:100Ω;精度:±1%;功率:62.5mW;温度系数:±200ppm/°C;电阻类型:厚膜电阻;")
      (fields
        (field (name "Manufacturer Part") "0402WGF1000TCE")
        (field (name "Manufacturer") "UNI-ROYAL(厚声)")
      )
      (libsource (lib "easyedapro") (part "0402WGF1000TCE"))
    )
    (comp (ref "R8")
      (value "100Ω")
      (footprint "easyedapro:R0402")
      (description "阻值:100Ω;精度:±1%;功率:62.5mW;温度系数:±200ppm/°C;电阻类型:厚膜电阻;")
      (fields
        (field (name "Manufacturer Part") "0402WGF1000TCE")
        (field (name "Manufacturer") "UNI-ROYAL(厚声)")
      )
      (libsource (lib "easyedapro") (part "0402WGF1000TCE"))
    )
    (comp (ref "R42")
      (value "12kΩ")
      (footprint "easyedapro:R0402")
      (description "电阻类型:厚膜电阻;阻值:12kΩ;精度:±1%;功率:62.5mW;")
      (fields
        (field (name "Manufacturer Part") "0402WGF1202TCE")
        (field (name "Manufacturer") "UNI-ROYAL(厚声)")
      )
      (libsource (lib "easyedapro") (part "0402WGF1202TCE"))
    )
    (comp (ref "R43")
      (value "12kΩ")
      (footprint "easyedapro:R0402")
      (description "电阻类型:厚膜电阻;阻值:12kΩ;精度:±1%;功率:62.5mW;")
      (fields
        (field (name "Manufacturer Part") "0402WGF1202TCE")
        (field (name "Manufacturer") "UNI-ROYAL(厚声)")
      )
      (libsource (lib "easyedapro") (part "0402WGF1202TCE"))
    )
    (comp (ref "SW1")
      (value "TS-1928-B")
      (footprint "easyedapro:KEY-SMD_4P-L2.8-W2.0-P1.20-LS3.0-TL")
      (description "触点电流:50mA;额定电压(DC):12V;绝缘电阻:-;电路结构:单刀单掷;安装方式:立贴;带灯:无;作用力:160gf;机械寿命:30万次;带支架:否;")
      (fields (field (name "Manufacturer") "XKB Connectivity(中国星坤)"))
      (libsource (lib "easyedapro") (part "TS-1928-B"))
    )
    (comp (ref "U7")
      (value "ESP8285H16")
      (footprint "easyedapro:QFN-32_L5.0-W5.0-P0.50-TL-EP3.7")
      (description "接口类型:-;")
      (fields (field (name "Manufacturer") "ESPRESSIF(乐鑫)"))
      (libsource (lib "easyedapro") (part "ESP8285H16"))
    )
    (comp (ref "U8")
      (value "SX1280IMLTRT")
      (footprint "easyedapro:QFN-24_L4.0-W4.0-P0.50-BL-EP2.6")
      (fields (field (name "Manufacturer") "SEMTECH"))
      (libsource (lib "easyedapro") (part "SX1280IMLTRT"))
    )
    (comp (ref "U10")
      (value "AT2401C")
      (footprint "easyedapro:QFN-16_L3.0-W3.0-P0.50-BL-EP1.7")
      (fields (field (name "Manufacturer") "杭州中科微"))
      (libsource (lib "easyedapro") (part "AT2401C"))
    )
    (comp (ref "U32")
      (value "ME6211A33M3G-N")
      (footprint "easyedapro:SOT-23-3_L2.9-W1.6-P1.90-LS2.8-BR")
      (description "输出类型:固定;工作电压:6V;输出电压:3.3V;输出电流:500mA;电源纹波抑制比(PSRR):70dB@(1kHz);输出极性:正极;")
      (fields (field (name "Manufacturer") "MICRONE(南京微盟)"))
      (libsource (lib "easyedapro") (part "ME6211A33M3G-N"))
    )
    (comp (ref "X2")
      (value "26MHz")
      (footprint "easyedapro:CRYSTAL-SMD_4P-L2.0-W1.6-BL")
      (description "频率:26MHz;频率公差:±10ppm;负载电容:12pF;")
      (fields (field (name "Manufacturer Part") "S2126000121080") (field (name "Manufacturer") "JGHC(晶光华)"))
      (libsource (lib "easyedapro") (part "S2126000121080"))
    )
    (comp (ref "X4")
      (value "52MHz")
      (footprint "easyedapro:OSC-SMD_4P-L2.0-W1.6-BL")
      (description "频率:52MHz;频率公差:±10ppm;负载电容:11pF;")
      (fields (field (name "Manufacturer Part") "7D052000K01") (field (name "Manufacturer") "HD(浩都频率)"))
      (libsource (lib "easyedapro") (part "7D052000K01"))
    )
  )
  (nets
    (net (code "1") (name "+3.3V") (class "Default")
      (node (ref "C365") (pin "2") (pinfunction "2_2") (pintype "input"))
      (node (ref "C366") (pin "2") (pinfunction "2_2") (pintype "input"))
      (node (ref "C394") (pin "1") (pinfunction "1_1") (pintype "input"))
      (node (ref "R133") (pin "1") (pinfunction "1_1") (pintype "input"))
      (node (ref "R134") (pin "1") (pinfunction "1_1") (pintype "input"))
      (node (ref "R135") (pin "2") (pinfunction "2_2") (pintype "input"))
      (node (ref "R136") (pin "2") (pinfunction "2_2") (pintype "input"))
      (node (ref "R137") (pin "2") (pinfunction "2_2") (pintype "input"))
      (node (ref "U2") (pin "2") (pinfunction "CSB_2") (pintype "unspecified"))
      (node (ref "U2") (pin "6") (pinfunction "VDDIO_6") (pintype "unspecified"))
      (node (ref "U2") (pin "8") (pinfunction "VDD_8") (pintype "unspecified"))
      (node (ref "U20") (pin "21") (pinfunction "AVDD_21") (pintype "input"))
      (node (ref "U20") (pin "24") (pinfunction "PVDD_24") (pintype "input"))
      (node (ref "U20") (pin "3") (pinfunction "DVDD_3") (pintype "input"))
    )
    (net (code "2") (name "+3.3V_MCU") (class "Default")
      (node (ref "C368") (pin "1") (pinfunction "1_1") (pintype "input"))
      (node (ref "R130") (pin "1") (pinfunction "1_1") (pintype "input"))
      (node (ref "R33") (pin "5") (pinfunction "VDDIO_5") (pintype "input"))
      (node (ref "R33") (pin "8") (pinfunction "VDD_8") (pintype "input"))
      (node (ref "U13") (pin "3") (pinfunction "C_3") (pintype "input"))
      (node (ref "U13") (pin "4") (pinfunction "D_4") (pintype "input"))
    )
    (net (code "3") (name "+5V") (class "Default")
      (node (ref "C322") (pin "2") (pinfunction "2_2") (pintype "input"))
      (node (ref "C350") (pin "1") (pinfunction "1_1") (pintype "input"))
      (node (ref "C357") (pin "2") (pinfunction "2_2") (pintype "input"))
      (node (ref "C358") (pin "2") (pinfunction "2_2") (pintype "input"))
      (node (ref "C395") (pin "2") (pinfunction "2_2") (pintype "input"))
      (node (ref "R128") (pin "2") (pinfunction "2_2") (pintype "input"))
      (node (ref "U26") (pin "3") (pinfunction "VIN_3") (pintype "unspecified"))
      (node (ref "U27") (pin "5") (pinfunction "FB_5") (pintype "unspecified"))
      (node (ref "U27") (pin "7") (pinfunction "VOUT_7") (pintype "unspecified"))
      (node (ref "U27") (pin "8") (pinfunction "VOUT_8") (pintype "unspecified"))
      (node (ref "U32") (pin "3") (pinfunction "VIN_3") (pintype "unspecified"))
    )
    (net (code "4") (name "+9V") (class "Default")
      (node (ref "C351") (pin "1") (pinfunction "1_1") (pintype "input"))
      (node (ref "C354") (pin "2") (pinfunction "2_2") (pintype "input"))
      (node (ref "C355") (pin "2") (pinfunction "2_2") (pintype "input"))
      (node (ref "R140") (pin "2") (pinfunction "2_2") (pintype "input"))
      (node (ref "R143") (pin "1") (pinfunction "1_1") (pintype "input"))
      (node (ref "U31") (pin "7") (pinfunction "VOUT_7") (pintype "unspecified"))
      (node (ref "U31") (pin "8") (pinfunction "VOUT_8") (pintype "unspecified"))
    )
    (net (code "5") (name "+VBAT") (class "Default")
      (node (ref "C340") (pin "1") (pinfunction "1_1") (pintype "input"))
      (node (ref "C346") (pin "1") (pinfunction "1_1") (pintype "input"))
      (node (ref "C352") (pin "2") (pinfunction "2_2") (pintype "input"))
      (node (ref "C353") (pin "2") (pinfunction "2_2") (pintype "input"))
      (node (ref "R129") (pin "2") (pinfunction "2_2") (pintype "input"))
      (node (ref "R141") (pin "2") (pinfunction "2_2") (pintype "input"))
      (node (ref "U27") (pin "12") (pinfunction "VIN_12") (pintype "unspecified"))
      (node (ref "U27") (pin "13") (pinfunction "VIN_13") (pintype "unspecified"))
      (node (ref "U31") (pin "12") (pinfunction "VIN_12") (pintype "unspecified"))
      (node (ref "U31") (pin "13") (pinfunction "VIN_13") (pintype "unspecified"))
    )
    (net (code "6") (name "3.3V") (class "Default")
      (node (ref "C12") (pin "1") (pinfunction "1_1") (pintype "input"))
      (node (ref "C323") (pin "2") (pinfunction "2_2") (pintype "input"))
      (node (ref "C396") (pin "2") (pinfunction "2_2") (pintype "input"))
      (node (ref "C4") (pin "1") (pinfunction "1_1") (pintype "input"))
      (node (ref "C5") (pin "1") (pinfunction "1_1") (pintype "input"))
      (node (ref "R1") (pin "2") (pinfunction "2_2") (pintype "input"))
      (node (ref "R4") (pin "1") (pinfunction "1_1") (pintype "input"))
      (node (ref "R42") (pin "1") (pinfunction "1_1") (pintype "input"))
      (node (ref "U10") (pin "16") (pinfunction "VCC_16") (pintype "input"))
      (node (ref "U26") (pin "2") (pinfunction "VOUT_2") (pintype "unspecified"))
      (node (ref "U32") (pin "2") (pinfunction "VOUT_2") (pintype "unspecified"))
      (node (ref "U7") (pin "1") (pinfunction "VDDA_1") (pintype "unspecified"))
      (node (ref "U7") (pin "11") (pinfunction "VDDPST_11") (pintype "unspecified"))
      (node (ref "U7") (pin "17") (pinfunction "VDDPST_17") (pintype "unspecified"))
      (node (ref "U7") (pin "29") (pinfunction "VDDD_29") (pintype "unspecified"))
      (node (ref "U7") (pin "3") (pinfunction "VDD3P3_3") (pintype "unspecified"))
      (node (ref "U7") (pin "30") (pinfunction "VDDA_30") (pintype "unspecified"))
      (node (ref "U7") (pin "4") (pinfunction "VDD3P3_4") (pintype "unspecified"))
      (node (ref "U8") (pin "11") (pinfunction "VBAT_IO_11") (pintype "input"))
      (node (ref "U8") (pin "15") (pinfunction "VBAT_15") (pintype "input"))
    )
    (net (code "7") (name "3V3") (class "Default")
      (node (ref "C369") (pin "2") (pinfunction "2_2") (pintype "input"))
      (node (ref "C372") (pin "1") (pinfunction "1_1") (pintype "input"))
      (node (ref "C375") (pin "2") (pinfunction "2_2") (pintype "input"))
      (node (ref "C376") (pin "2") (pinfunction "2_2") (pintype "input"))
      (node (ref "C377") (pin "2") (pinfunction "2_2") (pintype "input"))
      (node (ref "C378") (pin "2") (pinfunction "2_2") (pintype "input"))
      (node (ref "C379") (pin "2") (pinfunction "2_2") (pintype "input"))
      (node (ref "C380") (pin "2") (pinfunction "2_2") (pintype "input"))
      (node (ref "C381") (pin "2") (pinfunction "2_2") (pintype "input"))
      (node (ref "C382") (pin "2") (pinfunction "2_2") (pintype "input"))
      (node (ref "C383") (pin "2") (pinfunction "2_2") (pintype "input"))
      (node (ref "C384") (pin "2") (pinfunction "2_2") (pintype "input"))
      (node (ref "C385") (pin "2") (pinfunction "2_2") (pintype "input"))
      (node (ref "C386") (pin "2") (pinfunction "2_2") (pintype "input"))
      (node (ref "C387") (pin "2") (pinfunction "2_2") (pintype "input"))
      (node (ref "C388") (pin "2") (pinfunction "2_2") (pintype "input"))
      (node (ref "C389") (pin "2") (pinfunction "2_2") (pintype "input"))
      (node (ref "C390") (pin "2") (pinfunction "2_2") (pintype "input"))
      (node (ref "C391") (pin "2") (pinfunction "2_2") (pintype "input"))
      (node (ref "C392") (pin "2") (pinfunction "2_2") (pintype "input"))
      (node (ref "U1") (pin "1") (pinfunction "VBAT_1") (pintype "unspecified"))
      (node (ref "U1") (pin "13") (pinfunction "VDDA_13") (pintype "unspecified"))
      (node (ref "U1") (pin "19") (pinfunction "VDD_19") (pintype "unspecified"))
      (node (ref "U1") (pin "32") (pinfunction "VDD_32") (pintype "unspecified"))
      (node (ref "U1") (pin "48") (pinfunction "VDD_48") (pintype "unspecified"))
      (node (ref "U1") (pin "64") (pinfunction "VDD_64") (pintype "unspecified"))
      (node (ref "U3") (pin "13") (pinfunction "VDDIO_13") (pintype "unspecified"))
      (node (ref "U3") (pin "2") (pinfunction "VDD_2") (pintype "unspecified"))
      (node (ref "U3") (pin "4") (pinfunction "S1_4") (pintype "unspecified"))
      (node (ref "U5") (pin "3") (pinfunction "WP#(IO2)_3") (pintype "unspecified"))
      (node (ref "U5") (pin "7") (pinfunction "HOLD#/RESET#(IO3)_7") (pintype "unspecified"))
      (node (ref "U5") (pin "8") (pinfunction "VCC_8") (pintype "unspecified"))
    )
    (net (code "8") (name "5V-IN") (class "Default")
      (node (ref "H1") (pin "2") (pinfunction "2_2") (pintype "input"))
    )
    (net (code "9") (name "ANT") (class "Default")
      (node (ref "U7") (pin "2") (pinfunction "LNA_2") (pintype "unspecified"))
    )
    (net (code "10") (name "BOOT") (class "Default")
      (node (ref "R4") (pin "2") (pinfunction "2_2") (pintype "input"))
      (node (ref "SW1") (pin "3") (pinfunction "3_3") (pintype "input"))
      (node (ref "SW1") (pin "4") (pinfunction "4_4") (pintype "input"))
      (node (ref "U7") (pin "15") (pinfunction "GPIO0_15") (pintype "unspecified"))
    )
    (net (code "11") (name "BOOT0") (class "Default")
      (node (ref "R131") (pin "1") (pinfunction "1_1") (pintype "input"))
      (node (ref "R132") (pin "1") (pinfunction "1_1") (pintype "input"))
      (node (ref "U1") (pin "60") (pinfunction "BOOT0_60") (pintype "unspecified"))
      (node (ref "U13") (pin "1") (pinfunction "A_1") (pintype "input"))
      (node (ref "U13") (pin "2") (pinfunction "B_2") (pintype "input"))
    )
    (net (code "12") (name "BUSY-GPIO5") (class "Default")
      (node (ref "U7") (pin "24") (pinfunction "GPIO5_24") (pintype "unspecified"))
      (node (ref "U8") (pin "7") (pinfunction "BUSY_7") (pintype "input"))
    )
    (net (code "13") (name "DCC_FB") (class "Default")
      (node (ref "C6") (pin "2") (pinfunction "2_2") (pintype "input"))
      (node (ref "C82") (pin "2") (pinfunction "2_2") (pintype "input"))
      (node (ref "U8") (pin "12") (pinfunction "DCC_FB_12") (pintype "input"))
      (node (ref "U8") (pin "2") (pinfunction "VDD_IN_2") (pintype "input"))
    )
    (net (code "14") (name "DIO1-GPIO4") (class "Default")
      (node (ref "U7") (pin "16") (pinfunction "GPIO4_16") (pintype "unspecified"))
      (node (ref "U8") (pin "8") (pinfunction "DIO1_8") (pintype "input"))
    )
    (net (code "15") (name "DM") (class "Default")
      (node (ref "U1") (pin "44") (pinfunction "PA11_44") (pintype "bidirectional"))
    )
    (net (code "16") (name "DP") (class "Default")
      (node (ref "U1") (pin "45") (pinfunction "PA12_45") (pintype "bidirectional"))
    )
    (net (code "17") (name "GND") (class "Default")
      (node (ref "C12") (pin "2") (pinfunction "2_2") (pintype "input"))
      (node (ref "C2") (pin "1") (pinfunction "1_1") (pintype "input"))
      (node (ref "C3") (pin "2") (pinfunction "2_2") (pintype "input"))
      (node (ref "C322") (pin "1") (pinfunction "1_1") (pintype "input"))
      (node (ref "C323") (pin "1") (pinfunction "1_1") (pintype "input"))
      (node (ref "C338") (pin "1") (pinfunction "1_1") (pintype "input"))
      (node (ref "C340") (pin "2") (pinfunction "2_2") (pintype "input"))
      (node (ref "C344") (pin "1") (pinfunction "1_1") (pintype "input"))
      (node (ref "C346") (pin "2") (pinfunction "2_2") (pintype "input"))
      (node (ref "C350") (pin "2") (pinfunction "2_2") (pintype "input"))
      (node (ref "C351") (pin "2") (pinfunction "2_2") (pintype "input"))
      (node (ref "C352") (pin "1") (pinfunction "1_1") (pintype "input"))
      (node (ref "C353") (pin "1") (pinfunction "1_1") (pintype "input"))
      (node (ref "C354") (pin "1") (pinfunction "1_1") (pintype "input"))
      (node (ref "C355") (pin "1") (pinfunction "1_1") (pintype "input"))
      (node (ref "C357") (pin "1") (pinfunction "1_1") (pintype "input"))
      (node (ref "C358") (pin "1") (pinfunction "1_1") (pintype "input"))
      (node (ref "C365") (pin "1") (pinfunction "1_1") (pintype "input"))
      (node (ref "C366") (pin "1") (pinfunction "1_1") (pintype "input"))
      (node (ref "C368") (pin "2") (pinfunction "2_2") (pintype "input"))
      (node (ref "C369") (pin "1") (pinfunction "1_1") (pintype "input"))
      (node (ref "C371") (pin "2") (pinfunction "2_2") (pintype "input"))
      (node (ref "C372") (pin "2") (pinfunction "2_2") (pintype "input"))
      (node (ref "C373") (pin "2") (pinfunction "2_2") (pintype "input"))
      (node (ref "C374") (pin "2") (pinfunction "2_2") (pintype "input"))
      (node (ref "C375") (pin "1") (pinfunction "1_1") (pintype "input"))
      (node (ref "C376") (pin "1") (pinfunction "1_1") (pintype "input"))
      (node (ref "C377") (pin "1") (pinfunction "1_1") (pintype "input"))
      (node (ref "C378") (pin "1") (pinfunction "1_1") (pintype "input"))
      (node (ref "C379") (pin "1") (pinfunction "1_1") (pintype "input"))
      (node (ref "C380") (pin "1") (pinfunction "1_1") (pintype "input"))
      (node (ref "C381") (pin "1") (pinfunction "1_1") (pintype "input"))
      (node (ref "C382") (pin "1") (pinfunction "1_1") (pintype "input"))
      (node (ref "C383") (pin "1") (pinfunction "1_1") (pintype "input"))
      (node (ref "C384") (pin "1") (pinfunction "1_1") (pintype "input"))
      (node (ref "C385") (pin "1") (pinfunction "1_1") (pintype "input"))
      (node (ref "C386") (pin "1") (pinfunction "1_1") (pintype "input"))
      (node (ref "C387") (pin "1") (pinfunction "1_1") (pintype "input"))
      (node (ref "C388") (pin "1") (pinfunction "1_1") (pintype "input"))
      (node (ref "C389") (pin "1") (pinfunction "1_1") (pintype "input"))
      (node (ref "C390") (pin "1") (pinfunction "1_1") (pintype "input"))
      (node (ref "C391") (pin "1") (pinfunction "1_1") (pintype "input"))
      (node (ref "C392") (pin "1") (pinfunction "1_1") (pintype "input"))
      (node (ref "C393") (pin "1") (pinfunction "1_1") (pintype "input"))
      (node (ref "C394") (pin "2") (pinfunction "2_2") (pintype "input"))
      (node (ref "C395") (pin "1") (pinfunction "1_1") (pintype "input"))
      (node (ref "C396") (pin "1") (pinfunction "1_1") (pintype "input"))
      (node (ref "C4") (pin "2") (pinfunction "2_2") (pintype "input"))
      (node (ref "C5") (pin "2") (pinfunction "2_2") (pintype "input"))
      (node (ref "C6") (pin "1") (pinfunction "1_1") (pintype "input"))
      (node (ref "C7") (pin "1") (pinfunction "1_1") (pintype "input"))
      (node (ref "C8") (pin "1") (pinfunction "1_1") (pintype "input"))
      (node (ref "C82") (pin "1") (pinfunction "1_1") (pintype "input"))
      (node (ref "FL1") (pin "2") (pinfunction "GND_2") (pintype "input"))
      (node (ref "FL1") (pin "4") (pinfunction "GND_4") (pintype "input"))
      (node (ref "H1") (pin "1") (pinfunction "1_1") (pintype "input"))
      (node (ref "J1") (pin "2") (pinfunction "2_2") (pintype "unspecified"))
      (node (ref "J1") (pin "3") (pinfunction "3_3") (pintype "unspecified"))
      (node (ref "LED4") (pin "1") (pinfunction "C_1") (pintype "input"))
      (node (ref "Q1") (pin "1") (pinfunction "S_1") (pintype "unspecified"))
      (node (ref "Q1") (pin "2") (pinfunction "S_2") (pintype "unspecified"))
      (node (ref "Q1") (pin "3") (pinfunction "S_3") (pintype "unspecified"))
      (node (ref "Q2") (pin "1") (pinfunction "S_1") (pintype "unspecified"))
      (node (ref "Q2") (pin "2") (pinfunction "S_2") (pintype "unspecified"))
      (node (ref "Q2") (pin "3") (pinfunction "S_3") (pintype "unspecified"))
      (node (ref "Q3") (pin "1") (pinfunction "S_1") (pintype "unspecified"))
      (node (ref "Q3") (pin "2") (pinfunction "S_2") (pintype "unspecified"))
      (node (ref "Q3") (pin "3") (pinfunction "S_3") (pintype "unspecified"))
      (node (ref "Q4") (pin "1") (pinfunction "S_1") (pintype "unspecified"))
      (node (ref "Q4") (pin "2") (pinfunction "S_2") (pintype "unspecified"))
      (node (ref "Q4") (pin "3") (pinfunction "S_3") (pintype "unspecified"))
      (node (ref "R115") (pin "2") (pinfunction "2_2") (pintype "input"))
      (node (ref "R117") (pin "2") (pinfunction "2_2") (pintype "input"))
      (node (ref "R119") (pin "2") (pinfunction "2_2") (pintype "input"))
      (node (ref "R121") (pin "2") (pinfunction "2_2") (pintype "input"))
      (node (ref "R131") (pin "2") (pinfunction "2_2") (pintype "input"))
      (node (ref "R138") (pin "2") (pinfunction "2_2") (pintype "input"))
      (node (ref "R142") (pin "2") (pinfunction "2_2") (pintype "input"))
      (node (ref "R33") (pin "11") (pinfunction "RESV_11") (pintype "input"))
      (node (ref "R33") (pin "6") (pinfunction "GND_6") (pintype "input"))
      (node (ref "R33") (pin "7") (pinfunction "RESV_7") (pintype "input"))
      (node (ref "R43") (pin "2") (pinfunction "2_2") (pintype "input"))
      (node (ref "R5") (pin "1") (pinfunction "1_1") (pintype "input"))
      (node (ref "R6") (pin "2") (pinfunction "2_2") (pintype "input"))
      (node (ref "SW1") (pin "1") (pinfunction "1_1") (pintype "input"))
      (node (ref "SW1") (pin "2") (pinfunction "2_2") (pintype "input"))
      (node (ref "U1") (pin "12") (pinfunction "VSSA_12") (pintype "unspecified"))
      (node (ref "U1") (pin "18") (pinfunction "VSS_18") (pintype "unspecified"))
      (node (ref "U1") (pin "63") (pinfunction "VSS_63") (pintype "unspecified"))
      (node (ref "U10") (pin "1") (pinfunction "GND_1") (pintype "input"))
      (node (ref "U10") (pin "11") (pinfunction "GND_11") (pintype "input"))
      (node (ref "U10") (pin "12") (pinfunction "GND_12") (pintype "input"))
      (node (ref "U10") (pin "15") (pinfunction "GND_15") (pintype "input"))
      (node (ref "U10") (pin "17") (pinfunction "EP_17") (pintype "input"))
      (node (ref "U10") (pin "2") (pinfunction "GND_2") (pintype "input"))
      (node (ref "U10") (pin "3") (pinfunction "GND_3") (pintype "input"))
      (node (ref "U10") (pin "7") (pinfunction "GND_7") (pintype "input"))
      (node (ref "U10") (pin "8") (pinfunction "GND_8") (pintype "input"))
      (node (ref "U10") (pin "9") (pinfunction "GND_9") (pintype "input"))
      (node (ref "U13") (pin "5") (pinfunction "GND_5") (pintype "input"))
      (node (ref "U2") (pin "1") (pinfunction "GND_1") (pintype "unspecified"))
      (node (ref "U2") (pin "5") (pinfunction "SDO_5") (pintype "unspecified"))
      (node (ref "U2") (pin "7") (pinfunction "GND_7") (pintype "unspecified"))
      (node (ref "U20") (pin "20") (pinfunction "AGND_20") (pintype "input"))
      (node (ref "U20") (pin "23") (pinfunction "PGND_23") (pintype "input"))
      (node (ref "U20") (pin "29") (pinfunction "EP_29") (pintype "input"))
      (node (ref "U20") (pin "4") (pinfunction "DGND_4") (pintype "input"))
      (node (ref "U26") (pin "1") (pinfunction "VSS_1") (pintype "unspecified"))
      (node (ref "U27") (pin "1") (pinfunction "PS/SYNC_1") (pintype "unspecified"))
      (node (ref "U27") (pin "10") (pinfunction "PGND_10") (pintype "unspecified"))
      (node (ref "U27") (pin "15") (pinfunction "VSEL_15") (pintype "unspecified"))
      (node (ref "U27") (pin "4") (pinfunction "GND_4") (pintype "unspecified"))
      (node (ref "U27") (pin "6") (pinfunction "FB2_6") (pintype "unspecified"))
      (node (ref "U29") (pin "1") (pinfunction "A_1") (pintype "input"))
      (node (ref "U29") (pin "2") (pinfunction "B_2") (pintype "input"))
      (node (ref "U29") (pin "5") (pinfunction "GND_5") (pintype "input"))
      (node (ref "U3") (pin "11") (pinfunction "GND_11") (pintype "unspecified"))
      (node (ref "U3") (pin "9") (pinfunction "GND_9") (pintype "unspecified"))
      (node (ref "U31") (pin "1") (pinfunction "PS/SYNC_1") (pintype "unspecified"))
      (node (ref "U31") (pin "10") (pinfunction "PGND_10") (pintype "unspecified"))
      (node (ref "U31") (pin "15") (pinfunction "VSEL_15") (pintype "unspecified"))
      (node (ref "U31") (pin "4") (pinfunction "GND_4") (pintype "unspecified"))
      (node (ref "U31") (pin "6") (pinfunction "FB2_6") (pintype "unspecified"))
      (node (ref "U32") (pin "1") (pinfunction "VSS_1") (pintype "unspecified"))
      (node (ref "U5") (pin "4") (pinfunction "GND_4") (pintype "unspecified"))
      (node (ref "U5") (pin "9") (pinfunction "EP_9") (pintype "unspecified"))
      (node (ref "U7") (pin "33") (pinfunction "GND_33") (pintype "unspecified"))
      (node (ref "U8") (pin "13") (pinfunction "GND_13") (pintype "input"))
      (node (ref "U8") (pin "20") (pinfunction "GND_20") (pintype "input"))
      (node (ref "U8") (pin "21") (pinfunction "GND_21") (pintype "input"))
      (node (ref "U8") (pin "23") (pinfunction "GND_23") (pintype "input"))
      (node (ref "U8") (pin "24") (pinfunction "GND_24") (pintype "input"))
      (node (ref "U8") (pin "25") (pinfunction "GND_25") (pintype "input"))
      (node (ref "U8") (pin "5") (pinfunction "GND_5") (pintype "input"))
      (node (ref "X1") (pin "2") (pinfunction "VSS_2") (pintype "input"))
      (node (ref "X2") (pin "2") (pinfunction "GND_2") (pintype "input"))
      (node (ref "X2") (pin "4") (pinfunction "GND_4") (pintype "input"))
      (node (ref "X3") (pin "2") (pinfunction "GND_2") (pintype "input"))
      (node (ref "X3") (pin "4") (pinfunction "GND_4") (pintype "input"))
      (node (ref "X4") (pin "2") (pinfunction "GND_2") (pintype "input"))
      (node (ref "X4") (pin "4") (pinfunction "GND_4") (pintype "input"))
    )
    (net (code "18") (name "HMC5883L_INT") (class "Default")
      (node (ref "U1") (pin "24") (pinfunction "PC4_24") (pintype "bidirectional"))
      (node (ref "U3") (pin "15") (pinfunction "DRDY_15") (pintype "unspecified"))
    )
    (net (code "19") (name "I2C2_SDA") (class "Default")
      (node (ref "U1") (pin "30") (pinfunction "PB11_30") (pintype "bidirectional"))
    )
    (net (code "20") (name "ICM42688_CS") (class "Default")
      (node (ref "R33") (pin "12") (pinfunction "AP_CS_12") (pintype "input"))
      (node (ref "U1") (pin "10") (pinfunction "PC2_10") (pintype "bidirectional"))
    )
    (net (code "21") (name "ICM42688_INT") (class "Default")
      (node (ref "R33") (pin "4") (pinfunction "INT1/INT_4") (pintype "input"))
      (node (ref "U1") (pin "11") (pinfunction "PC3_11") (pintype "bidirectional"))
    )
    (net (code "22") (name "IIC1_SCL") (class "Default")
      (node (ref "U1") (pin "58") (pinfunction "PB6_58") (pintype "bidirectional"))
      (node (ref "U2") (pin "4") (pinfunction "SCK_4") (pintype "unspecified"))
    )
    (net (code "23") (name "IIC1_SDA") (class "Default")
      (node (ref "U1") (pin "59") (pinfunction "PB7_59") (pintype "bidirectional"))
      (node (ref "U2") (pin "3") (pinfunction "SDI_3") (pintype "unspecified"))
    )
    (net (code "24") (name "IIC2_SCL") (class "Default")
      (node (ref "U1") (pin "29") (pinfunction "PB10_29") (pintype "bidirectional"))
    )
    (net (code "25") (name "IIC3_SCL") (class "Default")
      (node (ref "U1") (pin "41") (pinfunction "PA8_41") (pintype "bidirectional"))
      (node (ref "U3") (pin "1") (pinfunction "SCL_1") (pintype "unspecified"))
    )
    (net (code "26") (name "IIC3_SDA") (class "Default")
      (node (ref "U1") (pin "40") (pinfunction "PC9_40") (pintype "bidirectional"))
      (node (ref "U3") (pin "16") (pinfunction "SDA_16") (pintype "unspecified"))
    )
    (net (code "27") (name "LED-GPIO16") (class "Default")
      (node (ref "LED3") (pin "2") (pinfunction "A_2") (pintype "input"))
      (node (ref "U7") (pin "8") (pinfunction "XDP_DCDC_8") (pintype "unspecified"))
    )
    (net (code "28") (name "M1") (class "Default")
      (node (ref "R114") (pin "2") (pinfunction "2_2") (pintype "input"))
    )
    (net (code "29") (name "M2") (class "Default")
      (node (ref "R116") (pin "2") (pinfunction "2_2") (pintype "input"))
    )
    (net (code "30") (name "M3") (class "Default")
      (node (ref "R118") (pin "2") (pinfunction "2_2") (pintype "input"))
    )
    (net (code "31") (name "M4") (class "Default")
      (node (ref "R120") (pin "2") (pinfunction "2_2") (pintype "input"))
    )
    (net (code "32") (name "MISO-GPIO12") (class "Default")
      (node (ref "U7") (pin "10") (pinfunction "MTDI_10") (pintype "unspecified"))
      (node (ref "U8") (pin "16") (pinfunction "MISO_TX_16") (pintype "input"))
    )
    (net (code "33") (name "MOSI-GPIO13") (class "Default")
      (node (ref "U7") (pin "12") (pinfunction "MTCK_12") (pintype "unspecified"))
      (node (ref "U8") (pin "17") (pinfunction "MOSI_RX_17") (pintype "input"))
    )
    (net (code "34") (name "NRST") (class "Default")
      (node (ref "C393") (pin "2") (pinfunction "2_2") (pintype "input"))
      (node (ref "R130") (pin "2") (pinfunction "2_2") (pintype "input"))
      (node (ref "U1") (pin "7") (pinfunction "NRST_7") (pintype "bidirectional"))
      (node (ref "U29") (pin "3") (pinfunction "C_3") (pintype "input"))
      (node (ref "U29") (pin "4") (pinfunction "D_4") (pintype "input"))
    )
    (net (code "35") (name "NSS-GPIO15") (class "Default")
      (node (ref "R5") (pin "2") (pinfunction "2_2") (pintype "input"))
      (node (ref "U7") (pin "13") (pinfunction "MTDO_13") (pintype "unspecified"))
      (node (ref "U8") (pin "19") (pinfunction "NSS_CTS_19") (pintype "input"))
    )
    (net (code "36") (name "Net-(C314-Pad2)") (class "Default")
      (node (ref "C314") (pin "2") (pinfunction "2_2") (pintype "input"))
      (node (ref "C317") (pin "2") (pinfunction "2_2") (pintype "input"))
      (node (ref "R139") (pin "2") (pinfunction "2_2") (pintype "input"))
    )
    (net (code "37") (name "Net-(C318-Pad1)") (class "Default")
      (node (ref "C318") (pin "1") (pinfunction "1_1") (pintype "input"))
      (node (ref "Q1") (pin "5") (pinfunction "D_5") (pintype "unspecified"))
      (node (ref "Q1") (pin "6") (pinfunction "D_6") (pintype "unspecified"))
      (node (ref "Q1") (pin "7") (pinfunction "D_7") (pintype "unspecified"))
      (node (ref "Q1") (pin "8") (pinfunction "D_8") (pintype "unspecified"))
      (node (ref "Q1") (pin "9") (pinfunction "D_9") (pintype "unspecified"))
    )
    (net (code "38") (name "Net-(C319-Pad1)") (class "Default")
      (node (ref "C319") (pin "1") (pinfunction "1_1") (pintype "input"))
      (node (ref "Q2") (pin "5") (pinfunction "D_5") (pintype "unspecified"))
      (node (ref "Q2") (pin "6") (pinfunction "D_6") (pintype "unspecified"))
      (node (ref "Q2") (pin "7") (pinfunction "D_7") (pintype "unspecified"))
      (node (ref "Q2") (pin "8") (pinfunction "D_8") (pintype "unspecified"))
      (node (ref "Q2") (pin "9") (pinfunction "D_9") (pintype "unspecified"))
    )
    (net (code "39") (name "Net-(C320-Pad1)") (class "Default")
      (node (ref "C320") (pin "1") (pinfunction "1_1") (pintype "input"))
      (node (ref "Q3") (pin "5") (pinfunction "D_5") (pintype "unspecified"))
      (node (ref "Q3") (pin "6") (pinfunction "D_6") (pintype "unspecified"))
      (node (ref "Q3") (pin "7") (pinfunction "D_7") (pintype "unspecified"))
      (node (ref "Q3") (pin "8") (pinfunction "D_8") (pintype "unspecified"))
      (node (ref "Q3") (pin "9") (pinfunction "D_9") (pintype "unspecified"))
    )
    (net (code "40") (name "Net-(C321-Pad1)") (class "Default")
      (node (ref "C321") (pin "1") (pinfunction "1_1") (pintype "input"))
      (node (ref "Q4") (pin "5") (pinfunction "D_5") (pintype "unspecified"))
      (node (ref "Q4") (pin "6") (pinfunction "D_6") (pintype "unspecified"))
      (node (ref "Q4") (pin "7") (pinfunction "D_7") (pintype "unspecified"))
      (node (ref "Q4") (pin "8") (pinfunction "D_8") (pintype "unspecified"))
      (node (ref "Q4") (pin "9") (pinfunction "D_9") (pintype "unspecified"))
    )
    (net (code "41") (name "Net-(FL1-IN)") (class "Default")
      (node (ref "FL1") (pin "1") (pinfunction "IN_1") (pintype "input"))
      (node (ref "U8") (pin "22") (pinfunction "RFIO_22") (pintype "input"))
    )
    (net (code "42") (name "Net-(FL1-OUT)") (class "Default")
      (node (ref "FL1") (pin "3") (pinfunction "OUT_3") (pintype "input"))
      (node (ref "U10") (pin "4") (pinfunction "TXRX_4") (pintype "input"))
    )
    (net (code "43") (name "Net-(H1-Pad3)") (class "Default")
      (node (ref "H1") (pin "3") (pinfunction "3_3") (pintype "input"))
      (node (ref "R7") (pin "2") (pinfunction "2_2") (pintype "input"))
    )
    (net (code "44") (name "Net-(H1-Pad4)") (class "Default")
      (node (ref "H1") (pin "4") (pinfunction "4_4") (pintype "input"))
      (node (ref "R8") (pin "2") (pinfunction "2_2") (pintype "input"))
    )
    (net (code "45") (name "Net-(LED3-K)") (class "Default")
      (node (ref "LED3") (pin "1") (pinfunction "K_1") (pintype "input"))
      (node (ref "R6") (pin "1") (pinfunction "1_1") (pintype "input"))
    )
    (net (code "46") (name "Net-(LED4-A)") (class "Default")
      (node (ref "LED4") (pin "2") (pinfunction "A_2") (pintype "input"))
      (node (ref "R132") (pin "2") (pinfunction "2_2") (pintype "input"))
    )
    (net (code "47") (name "Net-(Q1-G)") (class "Default")
      (node (ref "Q1") (pin "4") (pinfunction "G_4") (pintype "unspecified"))
      (node (ref "R114") (pin "1") (pinfunction "1_1") (pintype "input"))
      (node (ref "R115") (pin "1") (pinfunction "1_1") (pintype "input"))
    )
    (net (code "48") (name "Net-(Q2-G)") (class "Default")
      (node (ref "Q2") (pin "4") (pinfunction "G_4") (pintype "unspecified"))
      (node (ref "R116") (pin "1") (pinfunction "1_1") (pintype "input"))
      (node (ref "R117") (pin "1") (pinfunction "1_1") (pintype "input"))
    )
    (net (code "49") (name "Net-(Q3-G)") (class "Default")
      (node (ref "Q3") (pin "4") (pinfunction "G_4") (pintype "unspecified"))
      (node (ref "R118") (pin "1") (pinfunction "1_1") (pintype "input"))
      (node (ref "R119") (pin "1") (pinfunction "1_1") (pintype "input"))
    )
    (net (code "50") (name "Net-(Q4-G)") (class "Default")
      (node (ref "Q4") (pin "4") (pinfunction "G_4") (pintype "unspecified"))
      (node (ref "R120") (pin "1") (pinfunction "1_1") (pintype "input"))
      (node (ref "R121") (pin "1") (pinfunction "1_1") (pintype "input"))
    )
    (net (code "51") (name "Net-(U1A-PH0-OSC_IN(PH0))") (class "Default")
      (node (ref "U1") (pin "5") (pinfunction "PH0-OSC_IN(PH0)_5") (pintype "bidirectional"))
      (node (ref "X1") (pin "3") (pinfunction "3_3") (pintype "input"))
    )
    (net (code "52") (name "Net-(U1A-PH1-OSC_OUT(PH1))") (class "Default")
      (node (ref "U1") (pin "6") (pinfunction "PH1-OSC_OUT(PH1)_6") (pintype "bidirectional"))
      (node (ref "X1") (pin "1") (pinfunction "1_1") (pintype "output"))
    )
    (net (code "53") (name "Net-(U1A-VCAP_1)") (class "Default")
      (node (ref "C373") (pin "1") (pinfunction "1_1") (pintype "input"))
      (node (ref "U1") (pin "31") (pinfunction "VCAP_1_31") (pintype "unspecified"))
    )
    (net (code "54") (name "Net-(U1A-VCAP_2)") (class "Default")
      (node (ref "C374") (pin "1") (pinfunction "1_1") (pintype "input"))
      (node (ref "U1") (pin "47") (pinfunction "VCAP_2_47") (pintype "unspecified"))
    )
    (net (code "55") (name "Net-(U3-C1)") (class "Default")
      (node (ref "C371") (pin "1") (pinfunction "1_1") (pintype "input"))
      (node (ref "U3") (pin "10") (pinfunction "C1_10") (pintype "unspecified"))
    )
    (net (code "56") (name "Net-(U3-SETC)") (class "Default")
      (node (ref "C370") (pin "2") (pinfunction "2_2") (pintype "input"))
      (node (ref "U3") (pin "12") (pinfunction "SETC_12") (pintype "unspecified"))
    )
    (net (code "57") (name "Net-(U3-SETP)") (class "Default")
      (node (ref "C370") (pin "1") (pinfunction "1_1") (pintype "input"))
      (node (ref "U3") (pin "8") (pinfunction "SETP_8") (pintype "unspecified"))
    )
    (net (code "58") (name "Net-(U7-CHIP_EN)") (class "Default")
      (node (ref "R42") (pin "2") (pinfunction "2_2") (pintype "input"))
      (node (ref "U7") (pin "7") (pinfunction "CHIP_EN_7") (pintype "unspecified"))
    )
    (net (code "59") (name "Net-(U7-EXT_RSTB)") (class "Default")
      (node (ref "C3") (pin "1") (pinfunction "1_1") (pintype "input"))
      (node (ref "R1") (pin "1") (pinfunction "1_1") (pintype "input"))
      (node (ref "U7") (pin "32") (pinfunction "EXT_RSTB_32") (pintype "unspecified"))
    )
    (net (code "60") (name "Net-(U7-RES12K)") (class "Default")
      (node (ref "R43") (pin "1") (pinfunction "1_1") (pintype "input"))
      (node (ref "U7") (pin "31") (pinfunction "RES12K_31") (pintype "unspecified"))
    )
    (net (code "61") (name "Net-(U8-VR_PA)") (class "Default")
      (node (ref "C2") (pin "2") (pinfunction "2_2") (pintype "input"))
      (node (ref "U8") (pin "1") (pinfunction "VR_PA_1") (pintype "input"))
    )
    (net (code "62") (name "Net-(U8-XTA)") (class "Default")
      (node (ref "U8") (pin "4") (pinfunction "XTA_4") (pintype "input"))
      (node (ref "X4") (pin "3") (pinfunction "OUT_3") (pintype "input"))
    )
    (net (code "63") (name "Net-(U8-XTB)") (class "Default")
      (node (ref "U8") (pin "6") (pinfunction "XTB_6") (pintype "input"))
      (node (ref "X4") (pin "1") (pinfunction "IN_1") (pintype "input"))
    )
    (net (code "64") (name "Net-(U10-ANT)") (class "Default")
      (node (ref "J1") (pin "1") (pinfunction "1_1") (pintype "unspecified"))
      (node (ref "U10") (pin "10") (pinfunction "ANT_10") (pintype "input"))
    )
    (net (code "65") (name "Net-(U20-CLKIN)") (class "Default")
      (node (ref "U20") (pin "5") (pinfunction "CLKIN_5") (pintype "input"))
      (node (ref "X3") (pin "3") (pinfunction "OSC2_3") (pintype "input"))
    )
    (net (code "66") (name "Net-(U20-HSYNC#)") (class "Default")
      (node (ref "R136") (pin "1") (pinfunction "1_1") (pintype "input"))
      (node (ref "U20") (pin "18") (pinfunction "HSYNC#_18") (pintype "input"))
    )
    (net (code "67") (name "Net-(U20-LOS)") (class "Default")
      (node (ref "R134") (pin "2") (pinfunction "2_2") (pintype "input"))
      (node (ref "U20") (pin "12") (pinfunction "LOS_12") (pintype "input"))
    )
    (net (code "68") (name "Net-(U20-RESET#)") (class "Default")
      (node (ref "R135") (pin "1") (pinfunction "1_1") (pintype "input"))
      (node (ref "U20") (pin "19") (pinfunction "RESET#_19") (pintype "input"))
    )
    (net (code "69") (name "Net-(U20-SAG)") (class "Default")
      (node (ref "C314") (pin "1") (pinfunction "1_1") (pintype "input"))
      (node (ref "U20") (pin "25") (pinfunction "SAG_25") (pintype "input"))
    )
    (net (code "70") (name "Net-(U20-VIN)") (class "Default")
      (node (ref "C336") (pin "1") (pinfunction "1_1") (pintype "input"))
      (node (ref "U20") (pin "22") (pinfunction "VIN_22") (pintype "input"))
    )
    (net (code "71") (name "Net-(U20-VOUT)") (class "Default")
      (node (ref "C317") (pin "1") (pinfunction "1_1") (pintype "input"))
      (node (ref "U20") (pin "26") (pinfunction "VOUT_26") (pintype "input"))
    )
    (net (code "72") (name "Net-(U20-VSYNC#)") (class "Default")
      (node (ref "R137") (pin "1") (pinfunction "1_1") (pintype "input"))
      (node (ref "U20") (pin "17") (pinfunction "VSYNC#_17") (pintype "input"))
    )
    (net (code "73") (name "Net-(U20-XFB)") (class "Default")
      (node (ref "U20") (pin "6") (pinfunction "XFB_6") (pintype "input"))
      (node (ref "X3") (pin "1") (pinfunction "OSC1_1") (pintype "input"))
    )
    (net (code "74") (name "Net-(U27-EN)") (class "Default")
      (node (ref "R129") (pin "1") (pinfunction "1_1") (pintype "input"))
      (node (ref "U27") (pin "14") (pinfunction "EN_14") (pintype "unspecified"))
    )
    (net (code "75") (name "Net-(U27-L1)") (class "Default")
      (node (ref "U27") (pin "11") (pinfunction "L1_11") (pintype "unspecified"))
      (node (ref "U28") (pin "2") (pinfunction "2_2") (pintype "unspecified"))
    )
    (net (code "76") (name "Net-(U27-L2)") (class "Default")
      (node (ref "U27") (pin "9") (pinfunction "L2_9") (pintype "unspecified"))
      (node (ref "U28") (pin "1") (pinfunction "1_1") (pintype "unspecified"))
    )
    (net (code "77") (name "Net-(U27-PG)") (class "Default")
      (node (ref "R128") (pin "1") (pinfunction "1_1") (pintype "input"))
      (node (ref "U27") (pin "2") (pinfunction "PG_2") (pintype "unspecified"))
    )
    (net (code "78") (name "Net-(U27-VAUX)") (class "Default")
      (node (ref "C338") (pin "2") (pinfunction "2_2") (pintype "input"))
      (node (ref "U27") (pin "3") (pinfunction "VAUX_3") (pintype "unspecified"))
    )
    (net (code "79") (name "Net-(U31-EN)") (class "Default")
      (node (ref "R141") (pin "1") (pinfunction "1_1") (pintype "input"))
      (node (ref "U31") (pin "14") (pinfunction "EN_14") (pintype "unspecified"))
    )
    (net (code "80") (name "Net-(U31-FB)") (class "Default")
      (node (ref "R142") (pin "1") (pinfunction "1_1") (pintype "input"))
      (node (ref "R143") (pin "2") (pinfunction "2_2") (pintype "input"))
      (node (ref "U31") (pin "5") (pinfunction "FB_5") (pintype "unspecified"))
    )
    (net (code "81") (name "Net-(U31-L1)") (class "Default")
      (node (ref "U30") (pin "2") (pinfunction "2_2") (pintype "unspecified"))
      (node (ref "U31") (pin "11") (pinfunction "L1_11") (pintype "unspecified"))
    )
    (net (code "82") (name "Net-(U31-L2)") (class "Default")
      (node (ref "U30") (pin "1") (pinfunction "1_1") (pintype "unspecified"))
      (node (ref "U31") (pin "9") (pinfunction "L2_9") (pintype "unspecified"))
    )
    (net (code "83") (name "Net-(U31-PG)") (class "Default")
      (node (ref "R140") (pin "1") (pinfunction "1_1") (pintype "input"))
      (node (ref "U31") (pin "2") (pinfunction "PG_2") (pintype "unspecified"))
    )
    (net (code "84") (name "Net-(U31-VAUX)") (class "Default")
      (node (ref "C344") (pin "2") (pinfunction "2_2") (pintype "input"))
      (node (ref "U31") (pin "3") (pinfunction "VAUX_3") (pintype "unspecified"))
    )
    (net (code "85") (name "OSC-IN") (class "Default")
      (node (ref "C8") (pin "2") (pinfunction "2_2") (pintype "input"))
      (node (ref "U7") (pin "28") (pinfunction "XTAL_IN_28") (pintype "unspecified"))
      (node (ref "X2") (pin "1") (pinfunction "OSC1_1") (pintype "input"))
    )
    (net (code "86") (name "OSC-OUT") (class "Default")
      (node (ref "C7") (pin "2") (pinfunction "2_2") (pintype "input"))
      (node (ref "U7") (pin "27") (pinfunction "XTAL_OUT_27") (pintype "unspecified"))
      (node (ref "X2") (pin "3") (pinfunction "OSC2_3") (pintype "input"))
    )
    (net (code "87") (name "RX-GPIO3") (class "Default")
      (node (ref "R8") (pin "1") (pinfunction "1_1") (pintype "input"))
      (node (ref "U7") (pin "25") (pinfunction "U0RXD_25") (pintype "unspecified"))
    )
    (net (code "88") (name "RXEN-GPIO9") (class "Default")
      (node (ref "U10") (pin "6") (pinfunction "RXEN_6") (pintype "input"))
      (node (ref "U7") (pin "18") (pinfunction "SD_DATA_2_18") (pintype "unspecified"))
    )
    (net (code "89") (name "Rst_GPIO2") (class "Default")
      (node (ref "U7") (pin "14") (pinfunction "GPIO2_14") (pintype "unspecified"))
      (node (ref "U8") (pin "3") (pinfunction "NRESET_3") (pintype "input"))
    )
    (net (code "90") (name "SCK-GPIO14") (class "Default")
      (node (ref "U7") (pin "9") (pinfunction "MTMS_9") (pintype "unspecified"))
      (node (ref "U8") (pin "18") (pinfunction "SCK_RTSN_18") (pintype "input"))
    )
    (net (code "91") (name "SPI1_MISO") (class "Default")
      (node (ref "R33") (pin "14") (pinfunction "AP_SDA/AP_SDIO/AP_SDI_14") (pintype "input"))
      (node (ref "U1") (pin "22") (pinfunction "PA6_22") (pintype "bidirectional"))
    )
    (net (code "92") (name "SPI1_MOSI") (class "Default")
      (node (ref "R33") (pin "1") (pinfunction "AP_SDO/AP_AD0_1") (pintype "input"))
      (node (ref "U1") (pin "23") (pinfunction "PA7_23") (pintype "bidirectional"))
    )
    (net (code "93") (name "SPI1_SCK") (class "Default")
      (node (ref "R33") (pin "13") (pinfunction "AP_SCL/AP_SCLK_13") (pintype "input"))
      (node (ref "U1") (pin "21") (pinfunction "PA5_21") (pintype "bidirectional"))
    )
    (net (code "94") (name "SPI2_CS") (class "Default")
      (node (ref "U1") (pin "33") (pinfunction "PB12_33") (pintype "bidirectional"))
      (node (ref "U5") (pin "1") (pinfunction "CS#_1") (pintype "unspecified"))
    )
    (net (code "95") (name "SPI2_MISO") (class "Default")
      (node (ref "U1") (pin "35") (pinfunction "PB14_35") (pintype "bidirectional"))
      (node (ref "U5") (pin "2") (pinfunction "DO(IO1)_2") (pintype "unspecified"))
    )
    (net (code "96") (name "SPI2_MOSI") (class "Default")
      (node (ref "U1") (pin "36") (pinfunction "PB15_36") (pintype "bidirectional"))
      (node (ref "U5") (pin "5") (pinfunction "DI(IO0)_5") (pintype "unspecified"))
    )
    (net (code "97") (name "SPI2_SCK") (class "Default")
      (node (ref "U1") (pin "34") (pinfunction "PB13_34") (pintype "bidirectional"))
      (node (ref "U5") (pin "6") (pinfunction "CLK_6") (pintype "unspecified"))
    )
    (net (code "98") (name "SPI3_CS") (class "Default")
      (node (ref "R133") (pin "2") (pinfunction "2_2") (pintype "input"))
      (node (ref "U20") (pin "8") (pinfunction "CS#_8") (pintype "input"))
    )
    (net (code "99") (name "SPI3_MISO") (class "Default")
      (node (ref "U1") (pin "56") (pinfunction "PB4(NJTRST)_56") (pintype "bidirectional"))
      (node (ref "U20") (pin "9") (pinfunction "SDIN_9") (pintype "input"))
    )
    (net (code "100") (name "SPI3_MOSI") (class "Default")
      (node (ref "U1") (pin "57") (pinfunction "PB5_57") (pintype "bidirectional"))
      (node (ref "U20") (pin "11") (pinfunction "SDOUT_11") (pintype "input"))
    )
    (net (code "101") (name "SPI3_SCK") (class "Default")
      (node (ref "U1") (pin "55") (pinfunction "PB3(JTDOTRACESWO)_55") (pintype "bidirectional"))
      (node (ref "U20") (pin "10") (pinfunction "SCLK_10") (pintype "input"))
    )
    (net (code "102") (name "SWCLK") (class "Default")
      (node (ref "U1") (pin "49") (pinfunction "PA14(JTCK-SWCLK)_49") (pintype "bidirectional"))
    )
    (net (code "103") (name "SWDIO") (class "Default")
      (node (ref "U1") (pin "46") (pinfunction "PA13(JTMS-SWDIO)_46") (pintype "bidirectional"))
    )
    (net (code "104") (name "T3_CH3") (class "Default")
      (node (ref "U1") (pin "39") (pinfunction "PC8_39") (pintype "bidirectional"))
    )
    (net (code "105") (name "T3_CH4") (class "Default")
      (node (ref "U1") (pin "27") (pinfunction "PB1_27") (pintype "bidirectional"))
    )
    (net (code "106") (name "T8_CH1") (class "Default")
      (node (ref "U1") (pin "37") (pinfunction "PC6_37") (pintype "bidirectional"))
    )
    (net (code "107") (name "T8_CH2") (class "Default")
      (node (ref "U1") (pin "38") (pinfunction "PC7_38") (pintype "bidirectional"))
    )
    (net (code "108") (name "TX-GPIO1") (class "Default")
      (node (ref "R7") (pin "1") (pinfunction "1_1") (pintype "input"))
      (node (ref "U7") (pin "26") (pinfunction "U0TXD_26") (pintype "unspecified"))
    )
    (net (code "109") (name "TXEN-GPIO10") (class "Default")
      (node (ref "U10") (pin "5") (pinfunction "TXEN_5") (pintype "input"))
      (node (ref "U7") (pin "19") (pinfunction "SD_DATA_3_19") (pintype "unspecified"))
    )
    (net (code "110") (name "UART4_RX") (class "Default")
      (node (ref "U1") (pin "15") (pinfunction "PA1_15") (pintype "bidirectional"))
    )
    (net (code "111") (name "UART4_TX") (class "Default")
      (node (ref "U1") (pin "14") (pinfunction "PA0-WKUP(PA0)_14") (pintype "bidirectional"))
    )
    (net (code "112") (name "UART5_RX") (class "Default")
      (node (ref "U1") (pin "54") (pinfunction "PD2_54") (pintype "bidirectional"))
    )
    (net (code "113") (name "UART5_TX") (class "Default")
      (node (ref "U1") (pin "53") (pinfunction "PC12_53") (pintype "bidirectional"))
    )
    (net (code "114") (name "USART1_RX") (class "Default")
      (node (ref "U1") (pin "43") (pinfunction "PA10_43") (pintype "bidirectional"))
    )
    (net (code "115") (name "USART1_TX") (class "Default")
      (node (ref "U1") (pin "42") (pinfunction "PA9_42") (pintype "bidirectional"))
    )
    (net (code "116") (name "USART2_RX") (class "Default")
      (node (ref "U1") (pin "17") (pinfunction "PA3_17") (pintype "bidirectional"))
    )
    (net (code "117") (name "USART2_TX") (class "Default")
      (node (ref "U1") (pin "16") (pinfunction "PA2_16") (pintype "bidirectional"))
    )
    (net (code "118") (name "USART3_RX") (class "Default")
      (node (ref "U1") (pin "52") (pinfunction "PC11_52") (pintype "bidirectional"))
    )
    (net (code "119") (name "USART3_TX") (class "Default")
      (node (ref "U1") (pin "51") (pinfunction "PC10_51") (pintype "bidirectional"))
    )
    (net (code "120") (name "VBAT") (class "Default")
      (node (ref "C318") (pin "2") (pinfunction "2_2") (pintype "input"))
      (node (ref "C319") (pin "2") (pinfunction "2_2") (pintype "input"))
      (node (ref "C320") (pin "2") (pinfunction "2_2") (pintype "input"))
      (node (ref "C321") (pin "2") (pinfunction "2_2") (pintype "input"))
    )
    (net (code "121") (name "VIDEO_IN") (class "Default")
      (node (ref "C336") (pin "2") (pinfunction "2_2") (pintype "input"))
      (node (ref "R138") (pin "1") (pinfunction "1_1") (pintype "input"))
    )
    (net (code "122") (name "VTX") (class "Default")
      (node (ref "R139") (pin "1") (pinfunction "1_1") (pintype "input"))
    )
    (net (code "123") (name "WAIT0") (class "Default")
      (node (ref "U1") (pin "61") (pinfunction "PB8_61") (pintype "bidirectional"))
    )
    (net (code "124") (name "WAIT1") (class "Default")
      (node (ref "U1") (pin "62") (pinfunction "PB9_62") (pintype "bidirectional"))
    )
    (net (code "125") (name "unconnected-(CN1-Pad1)") (class "Default")
      (node (ref "CN1") (pin "1") (pinfunction "1_1") (pintype "input"))
    )
    (net (code "126") (name "unconnected-(CN1-Pad2)") (class "Default")
      (node (ref "CN1") (pin "2") (pinfunction "2_2") (pintype "input"))
    )
    (net (code "127") (name "unconnected-(MP1-Pad1)") (class "Default")
      (node (ref "MP1") (pin "1") (pinfunction "1_1") (pintype "input"))
    )
    (net (code "128") (name "unconnected-(MP2-Pad1)") (class "Default")
      (node (ref "MP2") (pin "1") (pinfunction "1_1") (pintype "input"))
    )
    (net (code "129") (name "unconnected-(MP3-Pad1)") (class "Default")
      (node (ref "MP3") (pin "1") (pinfunction "1_1") (pintype "input"))
    )
    (net (code "130") (name "unconnected-(MP4-Pad1)") (class "Default")
      (node (ref "MP4") (pin "1") (pinfunction "1_1") (pintype "input"))
    )
    (net (code "131") (name "unconnected-(R33-INT2{slash}FSYNC{slash}CLKIN-Pad9)") (class "Default")
      (node (ref "R33") (pin "9") (pinfunction "INT2/FSYNC/CLKIN_9") (pintype "input+no_connect"))
    )
    (net (code "132") (name "unconnected-(R33-RESV-Pad2)") (class "Default")
      (node (ref "R33") (pin "2") (pinfunction "RESV_2") (pintype "input+no_connect"))
    )
    (net (code "133") (name "unconnected-(R33-RESV-Pad3)") (class "Default")
      (node (ref "R33") (pin "3") (pinfunction "RESV_3") (pintype "input+no_connect"))
    )
    (net (code "134") (name "unconnected-(R33-RESV-Pad10)") (class "Default")
      (node (ref "R33") (pin "10") (pinfunction "RESV_10") (pintype "input+no_connect"))
    )
    (net (code "135") (name "unconnected-(U1A-PA4-Pad20)") (class "Default")
      (node (ref "U1") (pin "20") (pinfunction "PA4_20") (pintype "bidirectional"))
    )
    (net (code "136") (name "unconnected-(U1A-PA15(JTDI)-Pad50)") (class "Default")
      (node (ref "U1") (pin "50") (pinfunction "PA15(JTDI)_50") (pintype "bidirectional"))
    )
    (net (code "137") (name "unconnected-(U1A-PB0-Pad26)") (class "Default")
      (node (ref "U1") (pin "26") (pinfunction "PB0_26") (pintype "bidirectional"))
    )
    (net (code "138") (name "unconnected-(U1A-PB2-BOOT1(PB2)-Pad28)") (class "Default")
      (node (ref "U1") (pin "28") (pinfunction "PB2-BOOT1(PB2)_28") (pintype "bidirectional"))
    )
    (net (code "139") (name "unconnected-(U1A-PC0-Pad8)") (class "Default")
      (node (ref "U1") (pin "8") (pinfunction "PC0_8") (pintype "bidirectional"))
    )
    (net (code "140") (name "unconnected-(U1A-PC1-Pad9)") (class "Default")
      (node (ref "U1") (pin "9") (pinfunction "PC1_9") (pintype "bidirectional"))
    )
    (net (code "141") (name "unconnected-(U1A-PC5-Pad25)") (class "Default")
      (node (ref "U1") (pin "25") (pinfunction "PC5_25") (pintype "bidirectional"))
    )
    (net (code "142") (name "unconnected-(U1A-PC13-Pad2)") (class "Default")
      (node (ref "U1") (pin "2") (pinfunction "PC13_2") (pintype "bidirectional"))
    )
    (net (code "143") (name "unconnected-(U1A-PC14-OSC32_IN(PC14)-Pad3)") (class "Default")
      (node (ref "U1") (pin "3") (pinfunction "PC14-OSC32_IN(PC14)_3") (pintype "bidirectional+no_connect"))
    )
    (net (code "144") (name "unconnected-(U1A-PC15-OSC32_OUT(PC15)-Pad4)") (class "Default")
      (node (ref "U1") (pin "4") (pinfunction "PC15-OSC32_OUT(PC15)_4") (pintype "bidirectional+no_connect"))
    )
    (net (code "145") (name "unconnected-(U3-NC-Pad3)") (class "Default")
      (node (ref "U3") (pin "3") (pinfunction "NC_3") (pintype "unspecified+no_connect"))
    )
    (net (code "146") (name "unconnected-(U3-NC-Pad5)") (class "Default")
      (node (ref "U3") (pin "5") (pinfunction "NC_5") (pintype "unspecified+no_connect"))
    )
    (net (code "147") (name "unconnected-(U3-NC-Pad6)") (class "Default")
      (node (ref "U3") (pin "6") (pinfunction "NC_6") (pintype "unspecified+no_connect"))
    )
    (net (code "148") (name "unconnected-(U3-NC-Pad7)") (class "Default")
      (node (ref "U3") (pin "7") (pinfunction "NC_7") (pintype "unspecified+no_connect"))
    )
    (net (code "149") (name "unconnected-(U3-NC-Pad14)") (class "Default")
      (node (ref "U3") (pin "14") (pinfunction "NC_14") (pintype "unspecified+no_connect"))
    )
    (net (code "150") (name "unconnected-(U7-SD_CLK-Pad21)") (class "Default")
      (node (ref "U7") (pin "21") (pinfunction "SD_CLK_21") (pintype "unspecified"))
    )
    (net (code "151") (name "unconnected-(U7-SD_CMD-Pad20)") (class "Default")
      (node (ref "U7") (pin "20") (pinfunction "SD_CMD_20") (pintype "unspecified"))
    )
    (net (code "152") (name "unconnected-(U7-SD_DATA_0-Pad22)") (class "Default")
      (node (ref "U7") (pin "22") (pinfunction "SD_DATA_0_22") (pintype "unspecified"))
    )
    (net (code "153") (name "unconnected-(U7-SD_DATA_1-Pad23)") (class "Default")
      (node (ref "U7") (pin "23") (pinfunction "SD_DATA_1_23") (pintype "unspecified"))
    )
    (net (code "154") (name "unconnected-(U7-TOUT-Pad6)") (class "Default")
      (node (ref "U7") (pin "6") (pinfunction "TOUT_6") (pintype "unspecified"))
    )
    (net (code "155") (name "unconnected-(U7-VDD_RTC-Pad5)") (class "Default")
      (node (ref "U7") (pin "5") (pinfunction "VDD_RTC_5") (pintype "unspecified"))
    )
    (net (code "156") (name "unconnected-(U8-DCC_SW-Pad14)") (class "Default")
      (node (ref "U8") (pin "14") (pinfunction "DCC_SW_14") (pintype "input+no_connect"))
    )
    (net (code "157") (name "unconnected-(U8-DIO2-Pad9)") (class "Default")
      (node (ref "U8") (pin "9") (pinfunction "DIO2_9") (pintype "input+no_connect"))
    )
    (net (code "158") (name "unconnected-(U8-DIO3-Pad10)") (class "Default")
      (node (ref "U8") (pin "10") (pinfunction "DIO3_10") (pintype "input+no_connect"))
    )
    (net (code "159") (name "unconnected-(U10-DNC-Pad13)") (class "Default")
      (node (ref "U10") (pin "13") (pinfunction "DNC_13") (pintype "input+no_connect"))
    )
    (net (code "160") (name "unconnected-(U10-VDD-Pad14)") (class "Default")
      (node (ref "U10") (pin "14") (pinfunction "VDD_14") (pintype "input+no_connect"))
    )
    (net (code "161") (name "unconnected-(U20-CLKOUT-Pad7)") (class "Default")
      (node (ref "U20") (pin "7") (pinfunction "CLKOUT_7") (pintype "input+no_connect"))
    )
    (net (code "162") (name "unconnected-(U20-NC-Pad1)") (class "Default")
      (node (ref "U20") (pin "1") (pinfunction "NC_1") (pintype "input+no_connect"))
    )
    (net (code "163") (name "unconnected-(U20-NC-Pad2)") (class "Default")
      (node (ref "U20") (pin "2") (pinfunction "NC_2") (pintype "input+no_connect"))
    )
    (net (code "164") (name "unconnected-(U20-NC-Pad13)") (class "Default")
      (node (ref "U20") (pin "13") (pinfunction "NC_13") (pintype "input+no_connect"))
    )
    (net (code "165") (name "unconnected-(U20-NC-Pad14)") (class "Default")
      (node (ref "U20") (pin "14") (pinfunction "NC_14") (pintype "input+no_connect"))
    )
    (net (code "166") (name "unconnected-(U20-NC-Pad15)") (class "Default")
      (node (ref "U20") (pin "15") (pinfunction "NC_15") (pintype "input+no_connect"))
    )
    (net (code "167") (name "unconnected-(U20-NC-Pad16)") (class "Default")
      (node (ref "U20") (pin "16") (pinfunction "NC_16") (pintype "input+no_connect"))
    )
    (net (code "168") (name "unconnected-(U20-NC-Pad27)") (class "Default")
      (node (ref "U20") (pin "27") (pinfunction "NC_27") (pintype "input+no_connect"))
    )
    (net (code "169") (name "unconnected-(U20-NC-Pad28)") (class "Default")
      (node (ref "U20") (pin "28") (pinfunction "NC_28") (pintype "input+no_connect"))
    )
  )
)
